# kulgurpower2-unrouted.net
KiCad netlist of a schematic drawn in EAGLE
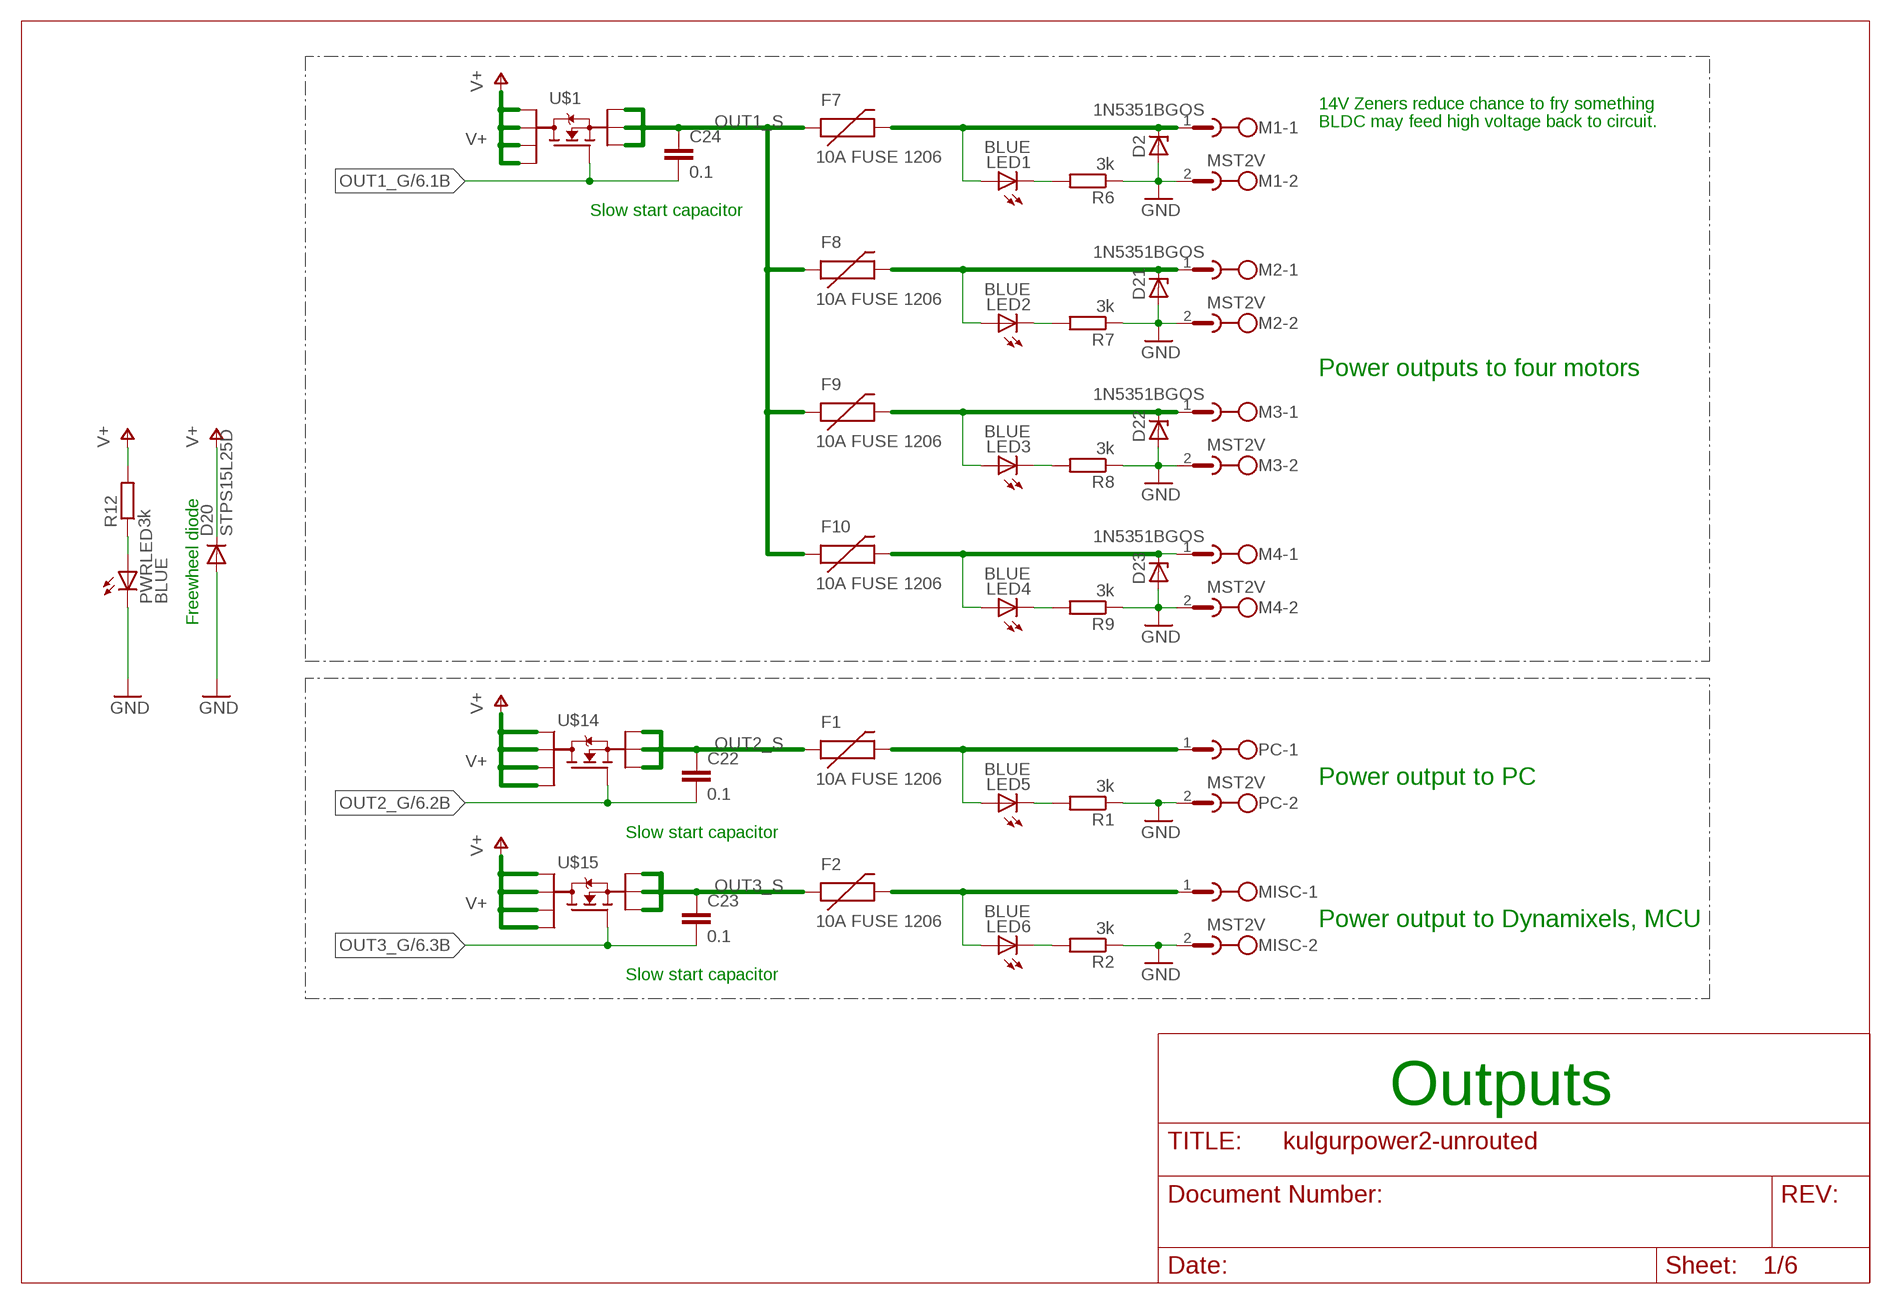
[diagram p0: schematic, sheet 1]
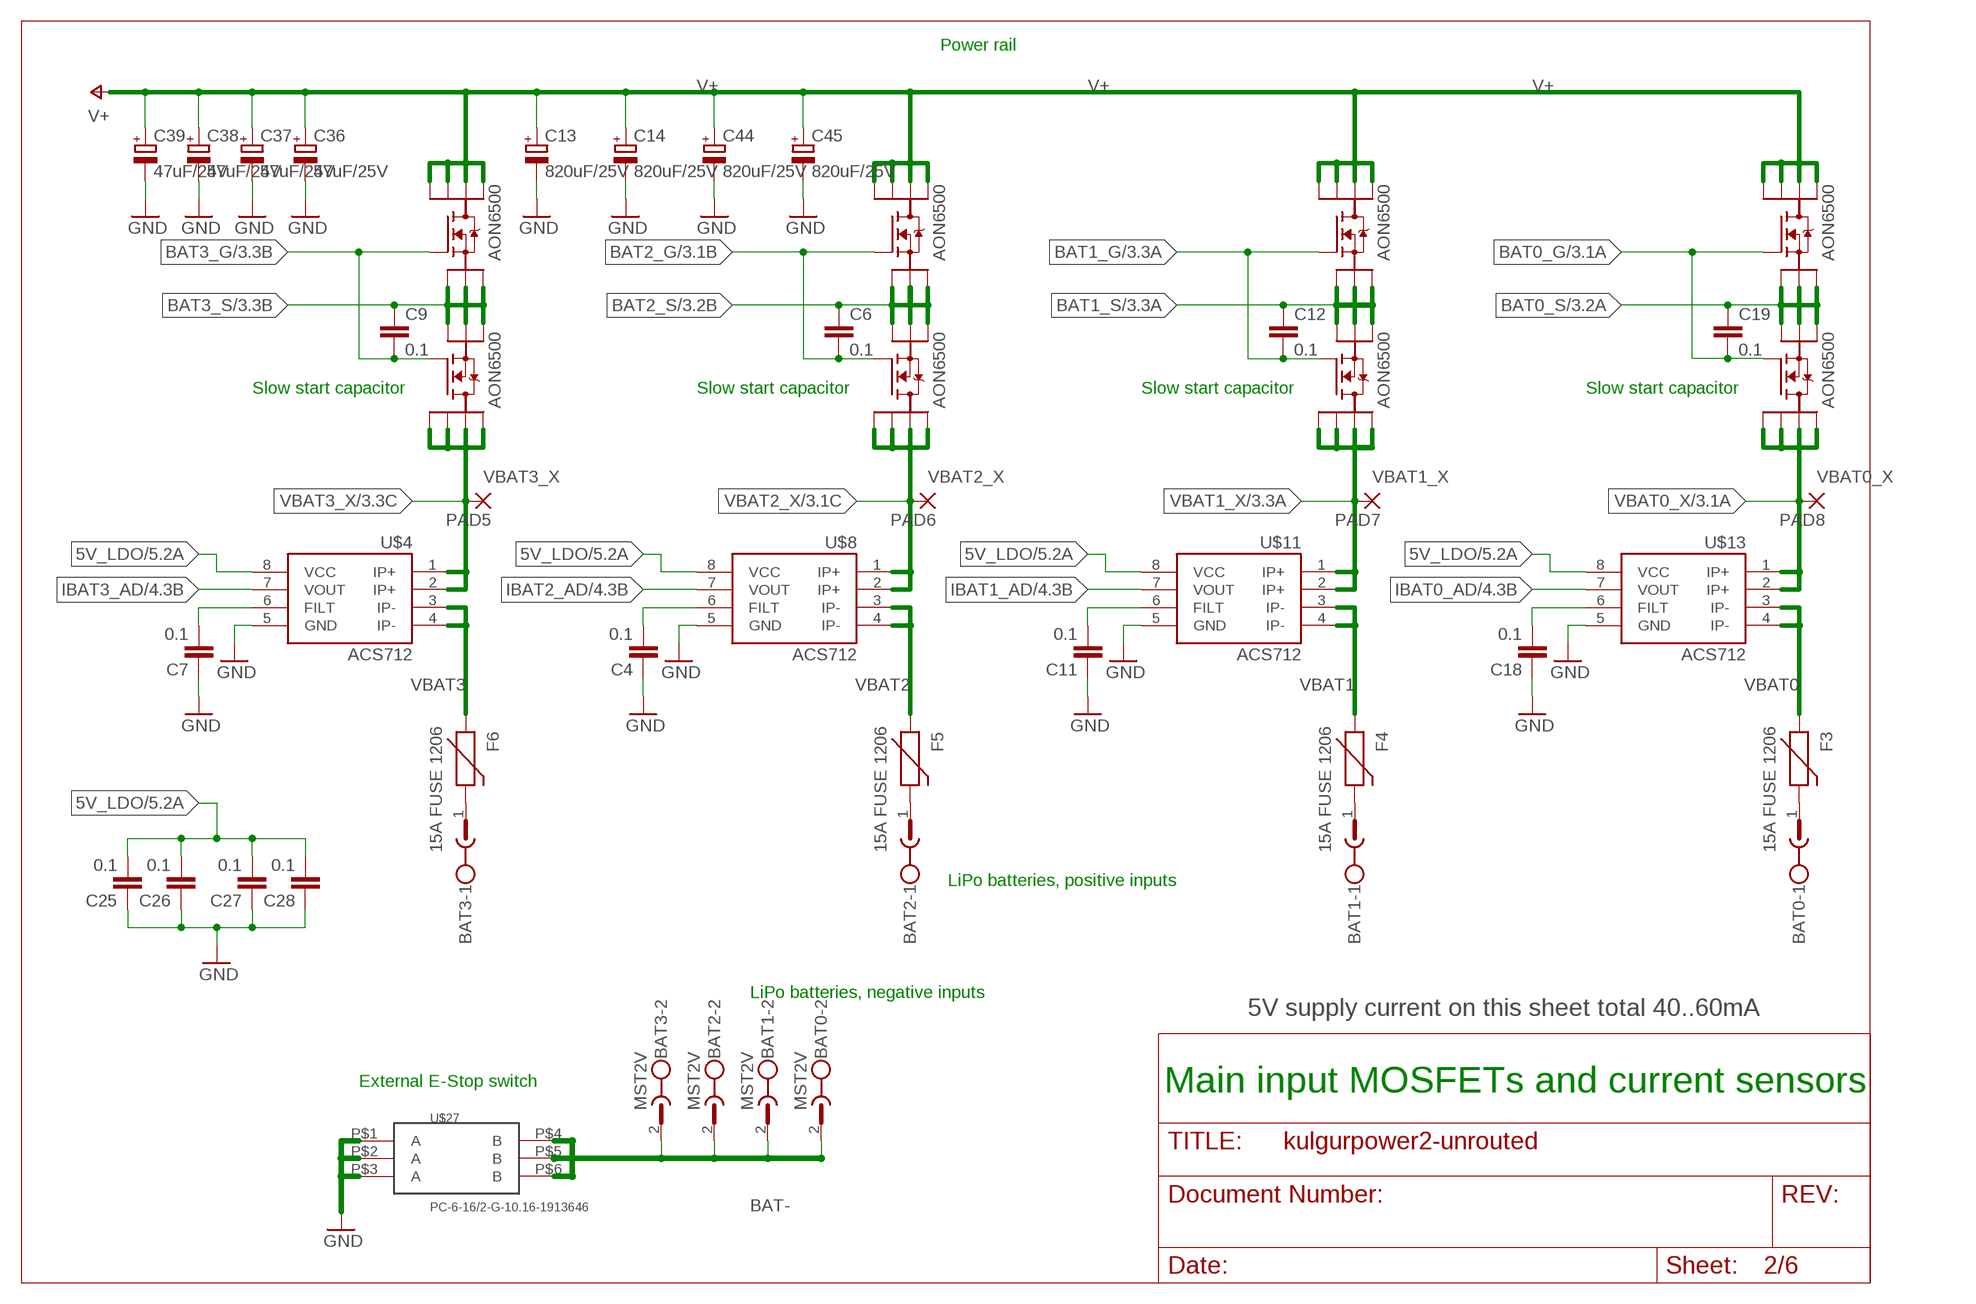
[diagram p1: schematic, sheet 2]
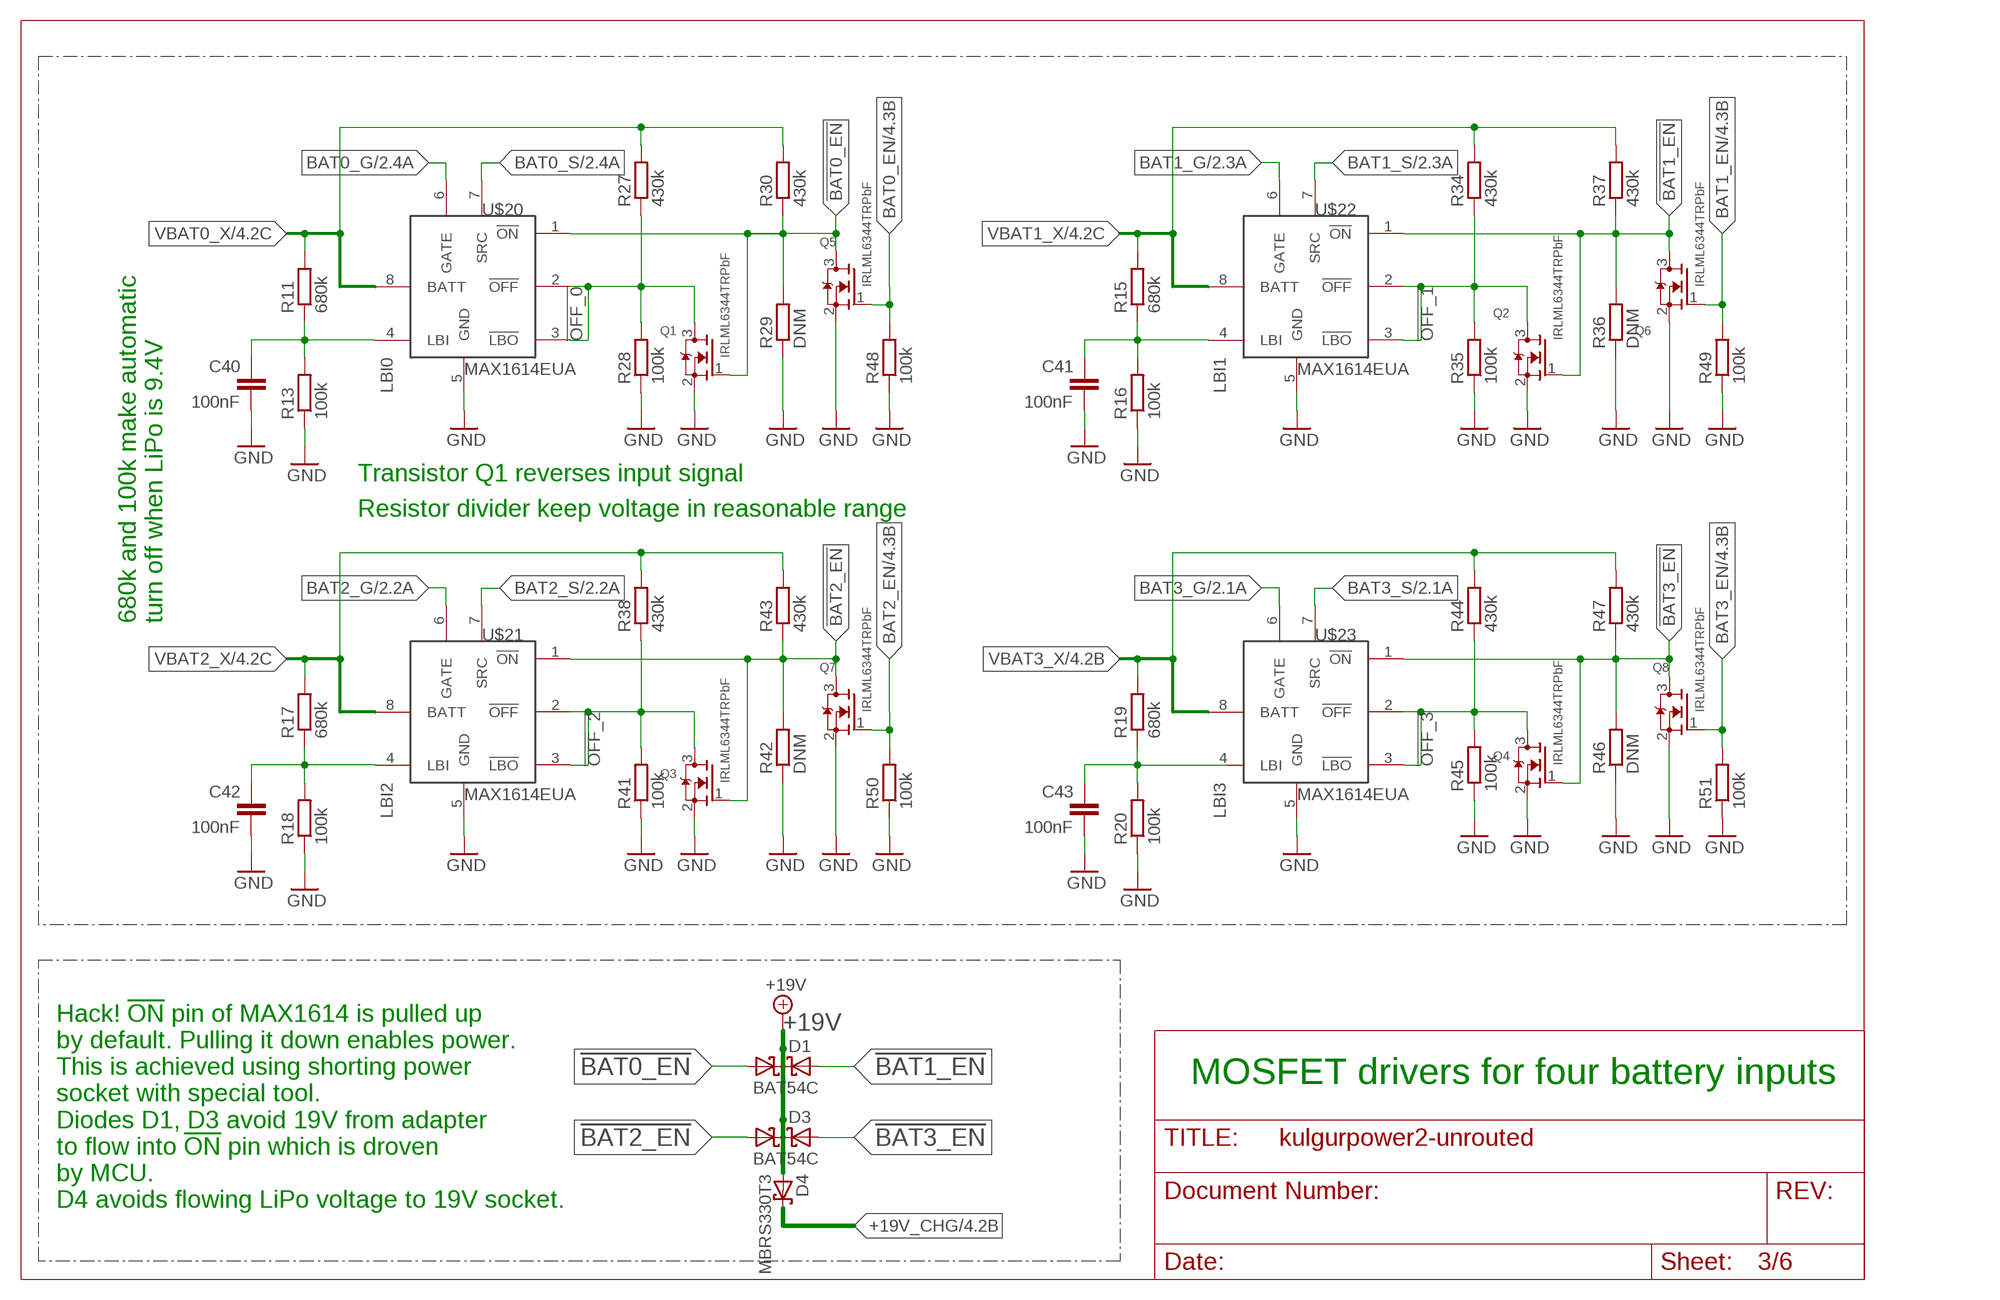
[diagram p2: schematic, sheet 3]
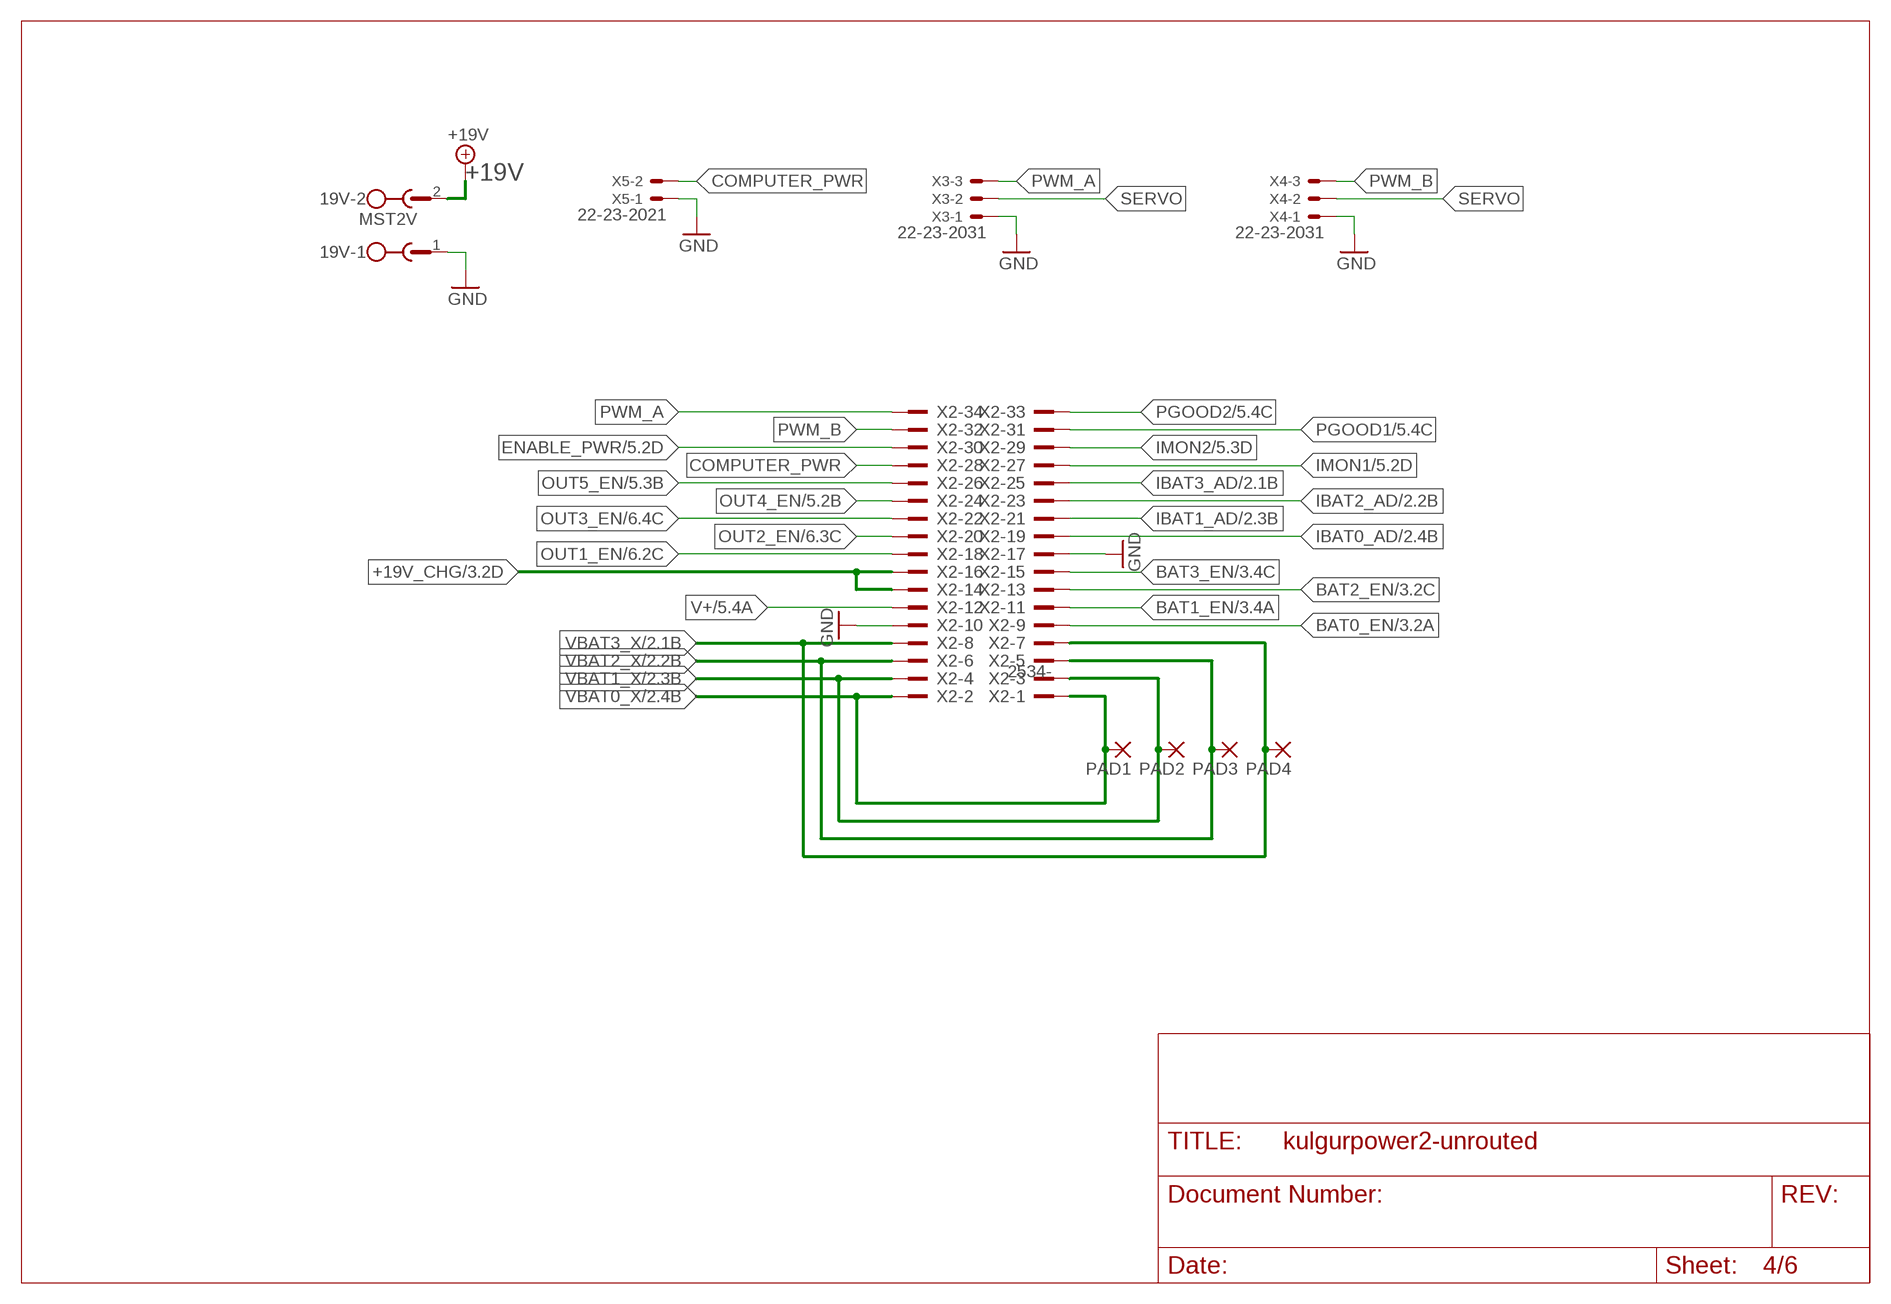
[diagram p3: schematic, sheet 4]
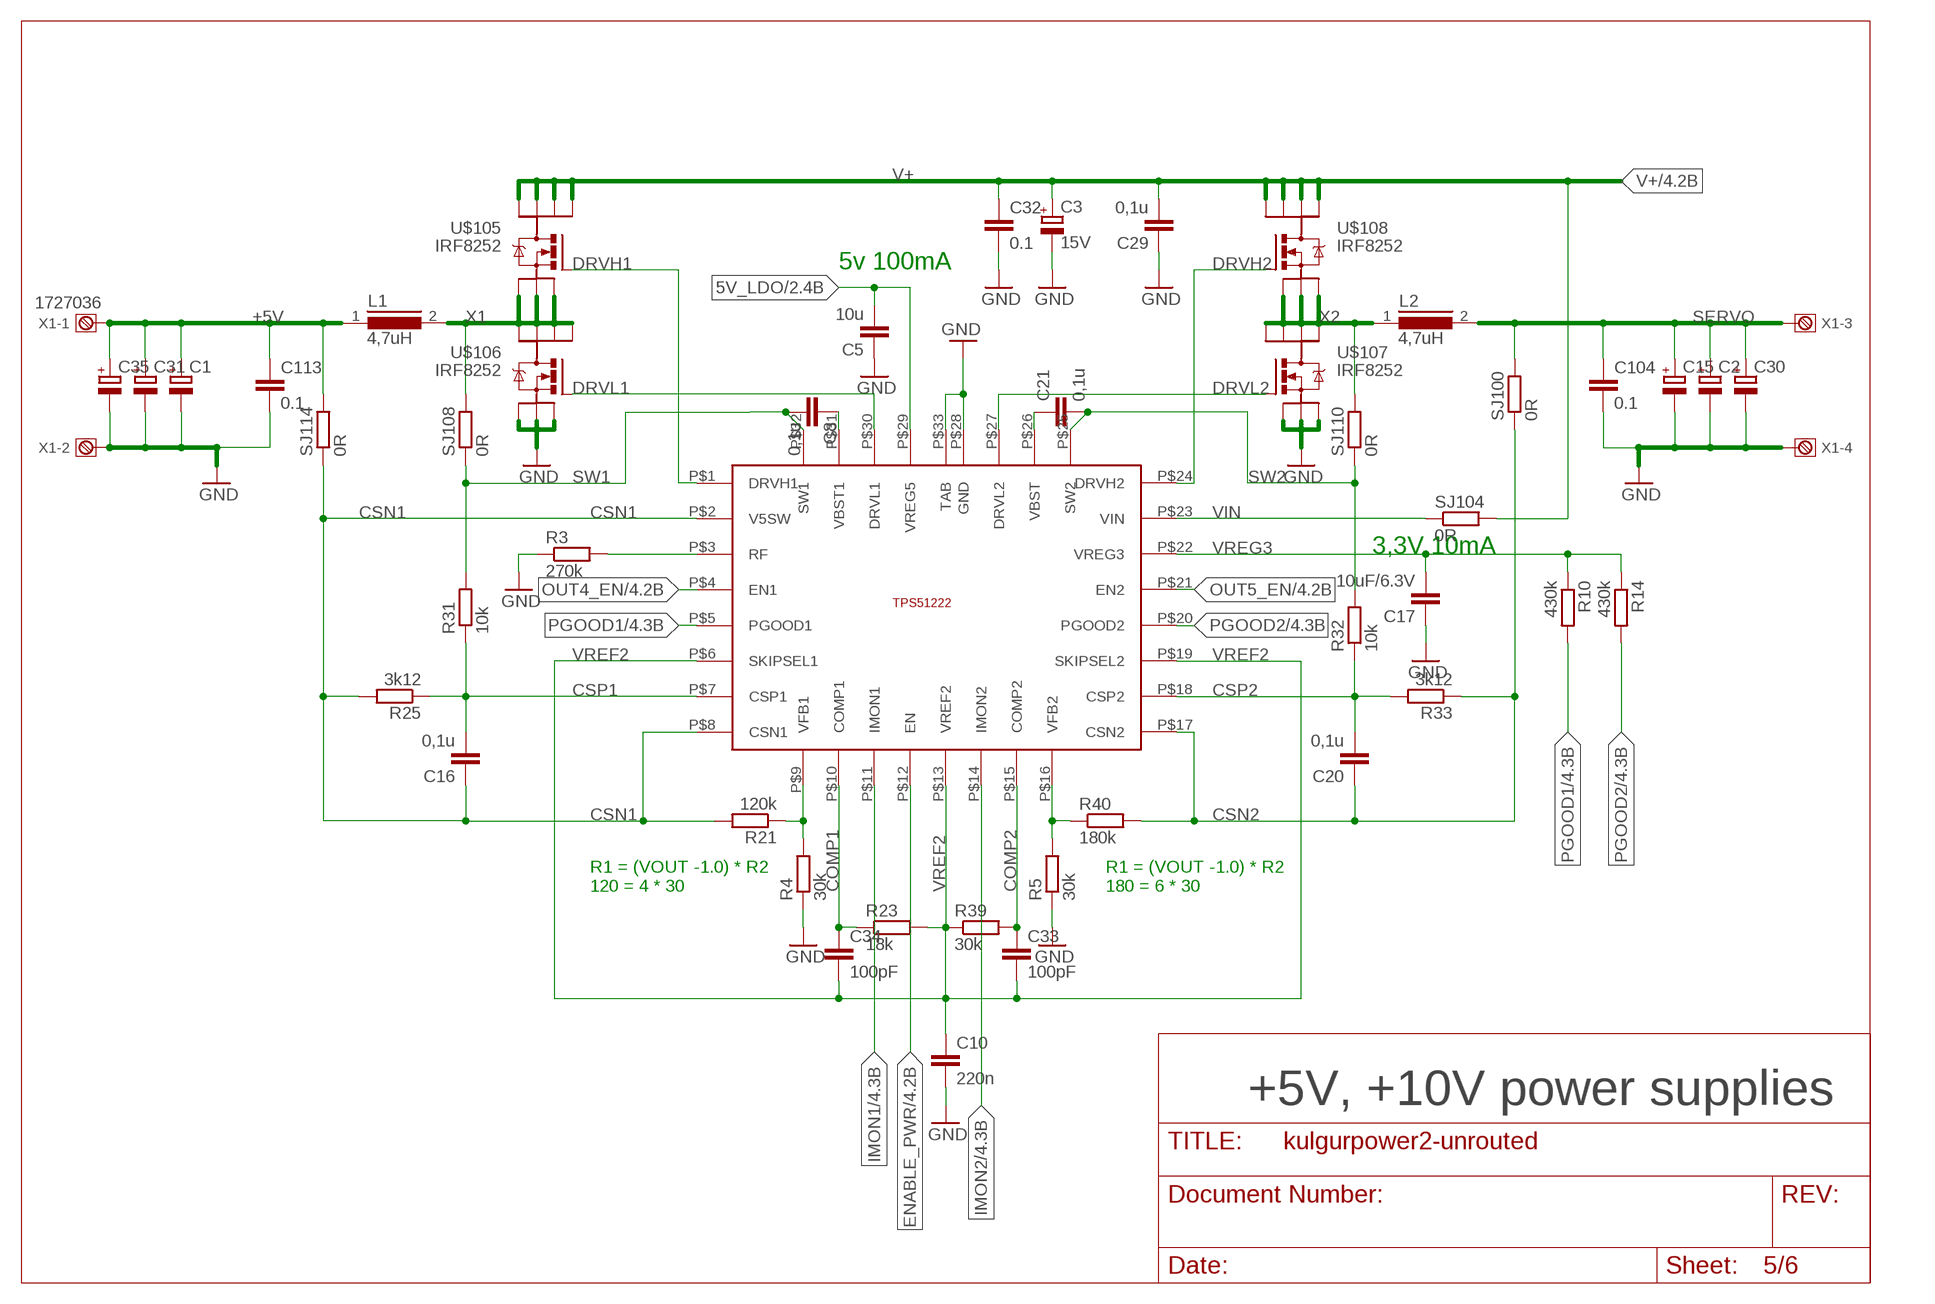
[diagram p4: schematic, sheet 5]
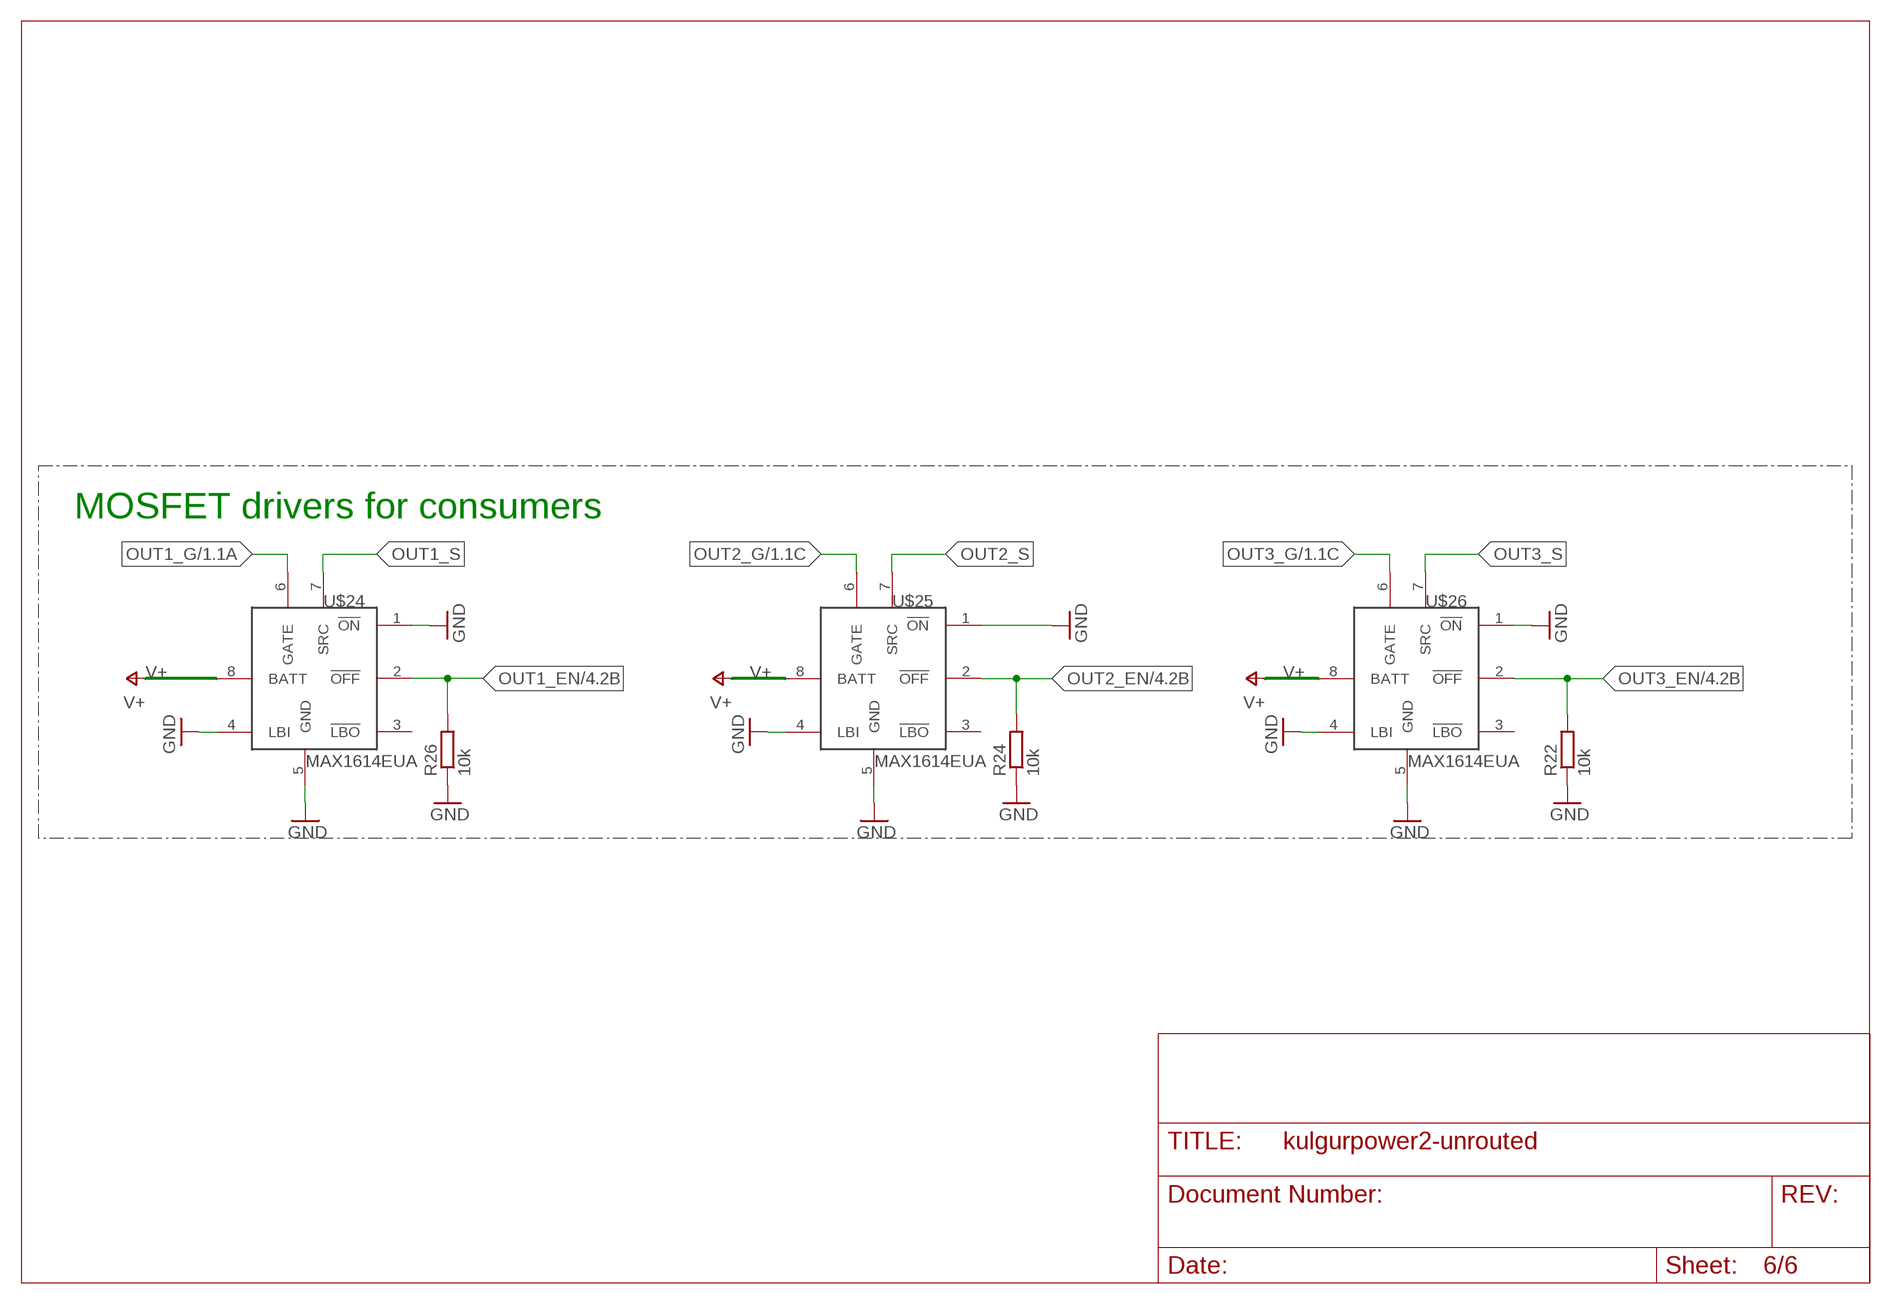
[diagram p5: schematic, sheet 6]

(export (version "E")
  (design (tool "Eeschema 10.0.6"))
  (components
    (comp (ref "C1")
      (value "CPOL-EUC/6032-28R")
      (footprint "eagle-import:C_6032-28R")
      (libsource (lib "eagle-import") (part "CPOL-EUC/6032-28R"))
    )
    (comp (ref "C2")
      (value "CPOL-EUC/6032-28R")
      (footprint "eagle-import:C_6032-28R")
      (libsource (lib "eagle-import") (part "CPOL-EUC/6032-28R"))
    )
    (comp (ref "C3")
      (value "15V")
      (footprint "eagle-import:C_6032-28R")
      (libsource (lib "eagle-import") (part "CPOL-EUC/6032-28R"))
    )
    (comp (ref "C5")
      (value "10u")
      (footprint "eagle-import:C1210")
      (libsource (lib "eagle-import") (part "C-EUC1210"))
    )
    (comp (ref "C8")
      (value "0,1u")
      (footprint "eagle-import:C0603")
      (libsource (lib "eagle-import") (part "C-EUC0603"))
    )
    (comp (ref "C10")
      (value "220n")
      (footprint "eagle-import:C0603")
      (libsource (lib "eagle-import") (part "C-EUC0603"))
    )
    (comp (ref "C15")
      (value "CPOL-EUC/6032-28R")
      (footprint "eagle-import:C_6032-28R")
      (libsource (lib "eagle-import") (part "CPOL-EUC/6032-28R"))
    )
    (comp (ref "C16")
      (value "0,1u")
      (footprint "eagle-import:C0603")
      (libsource (lib "eagle-import") (part "C-EUC0603"))
    )
    (comp (ref "C17")
      (value "10uF/6.3V")
      (footprint "eagle-import:C1210")
      (libsource (lib "eagle-import") (part "C-EUC1210"))
    )
    (comp (ref "C20")
      (value "0,1u")
      (footprint "eagle-import:C0603")
      (libsource (lib "eagle-import") (part "C-EUC0603"))
    )
    (comp (ref "C21")
      (value "0,1u")
      (footprint "eagle-import:C0603")
      (libsource (lib "eagle-import") (part "C-EUC0603"))
    )
    (comp (ref "C29")
      (value "0,1u")
      (footprint "eagle-import:C0603")
      (libsource (lib "eagle-import") (part "C-EUC0603"))
    )
    (comp (ref "C30")
      (value "CPOL-EUC/6032-28R")
      (footprint "eagle-import:C_6032-28R")
      (libsource (lib "eagle-import") (part "CPOL-EUC/6032-28R"))
    )
    (comp (ref "C31")
      (value "CPOL-EUC/6032-28R")
      (footprint "eagle-import:C_6032-28R")
      (libsource (lib "eagle-import") (part "CPOL-EUC/6032-28R"))
    )
    (comp (ref "C32")
      (value "0.1")
      (footprint "eagle-import:C0603")
      (libsource (lib "eagle-import") (part "C-EUC0603"))
    )
    (comp (ref "C33")
      (value "100pF")
      (footprint "eagle-import:0805")
      (libsource (lib "eagle-import") (part "CAP0805"))
    )
    (comp (ref "C34")
      (value "100pF")
      (footprint "eagle-import:0805")
      (libsource (lib "eagle-import") (part "CAP0805"))
    )
    (comp (ref "C35")
      (value "CPOL-EUC/6032-28R")
      (footprint "eagle-import:C_6032-28R")
      (libsource (lib "eagle-import") (part "CPOL-EUC/6032-28R"))
    )
    (comp (ref "C104")
      (value "0.1")
      (footprint "eagle-import:C0603")
      (libsource (lib "eagle-import") (part "C-EUC0603"))
    )
    (comp (ref "C113")
      (value "0.1")
      (footprint "eagle-import:C0603")
      (libsource (lib "eagle-import") (part "C-EUC0603"))
    )
    (comp (ref "L1")
      (value "4,7uH")
      (footprint "eagle-import:DR125")
      (libsource (lib "eagle-import") (part "DR125"))
    )
    (comp (ref "L2")
      (value "4,7uH")
      (footprint "eagle-import:DR125")
      (libsource (lib "eagle-import") (part "DR125"))
    )
    (comp (ref "R3")
      (value "270k")
      (footprint "eagle-import:R0603")
      (libsource (lib "eagle-import") (part "R-EU_R0603"))
    )
    (comp (ref "R4")
      (value "30k")
      (footprint "eagle-import:R0603")
      (libsource (lib "eagle-import") (part "R-EU_R0603"))
    )
    (comp (ref "R5")
      (value "30k")
      (footprint "eagle-import:R0603")
      (libsource (lib "eagle-import") (part "R-EU_R0603"))
    )
    (comp (ref "R10")
      (value "430k")
      (footprint "eagle-import:R0603")
      (libsource (lib "eagle-import") (part "R-EU_R0603"))
    )
    (comp (ref "R14")
      (value "430k")
      (footprint "eagle-import:R0603")
      (libsource (lib "eagle-import") (part "R-EU_R0603"))
    )
    (comp (ref "R21")
      (value "120k")
      (footprint "eagle-import:R0603")
      (libsource (lib "eagle-import") (part "R-EU_R0603"))
    )
    (comp (ref "R23")
      (value "18k")
      (footprint "eagle-import:R0603")
      (libsource (lib "eagle-import") (part "R-EU_R0603"))
    )
    (comp (ref "R25")
      (value "3k12")
      (footprint "eagle-import:R0603")
      (libsource (lib "eagle-import") (part "R-EU_R0603"))
    )
    (comp (ref "R31")
      (value "10k")
      (footprint "eagle-import:R0603")
      (libsource (lib "eagle-import") (part "R-EU_R0603"))
    )
    (comp (ref "R32")
      (value "10k")
      (footprint "eagle-import:R0603")
      (libsource (lib "eagle-import") (part "R-EU_R0603"))
    )
    (comp (ref "R33")
      (value "3k12")
      (footprint "eagle-import:R0603")
      (libsource (lib "eagle-import") (part "R-EU_R0603"))
    )
    (comp (ref "R39")
      (value "30k")
      (footprint "eagle-import:R0603")
      (libsource (lib "eagle-import") (part "R-EU_R0603"))
    )
    (comp (ref "R40")
      (value "180k")
      (footprint "eagle-import:R0603")
      (libsource (lib "eagle-import") (part "R-EU_R0603"))
    )
    (comp (ref "SJ100")
      (value "0R")
      (footprint "eagle-import:R0603")
      (libsource (lib "eagle-import") (part "R-EU_R0603"))
    )
    (comp (ref "SJ104")
      (value "0R")
      (footprint "eagle-import:R0603")
      (libsource (lib "eagle-import") (part "R-EU_R0603"))
    )
    (comp (ref "SJ108")
      (value "0R")
      (footprint "eagle-import:R0603")
      (libsource (lib "eagle-import") (part "R-EU_R0603"))
    )
    (comp (ref "SJ110")
      (value "0R")
      (footprint "eagle-import:R0603")
      (libsource (lib "eagle-import") (part "R-EU_R0603"))
    )
    (comp (ref "SJ114")
      (value "0R")
      (footprint "eagle-import:R0603")
      (libsource (lib "eagle-import") (part "R-EU_R0603"))
    )
    (comp (ref "U$17")
      (value "TPS51222RTVT")
      (footprint "eagle-import:QFN-32")
      (libsource (lib "eagle-import") (part "TPS51222RTVT"))
    )
    (comp (ref "U$105")
      (value "IRF8252")
      (footprint "eagle-import:SO8")
      (libsource (lib "eagle-import") (part "IRF8252"))
    )
    (comp (ref "U$106")
      (value "IRF8252")
      (footprint "eagle-import:SO8")
      (libsource (lib "eagle-import") (part "IRF8252"))
    )
    (comp (ref "U$107")
      (value "IRF8252")
      (footprint "eagle-import:SO8")
      (libsource (lib "eagle-import") (part "IRF8252"))
    )
    (comp (ref "U$108")
      (value "IRF8252")
      (footprint "eagle-import:SO8")
      (libsource (lib "eagle-import") (part "IRF8252"))
    )
    (comp (ref "X1")
      (value "1727036")
      (footprint "eagle-import:1727036")
      (fields (field (name "MF") "FARNELL"))
      (libsource (lib "eagle-import") (part "1727036"))
    )
    (comp (ref "19V")
      (value "MST2V")
      (footprint "eagle-import:MSTBV2")
      (libsource (lib "eagle-import") (part "MST2V"))
    )
    (comp (ref "PAD1")
      (value "1,6/0,9")
      (footprint "eagle-import:1,6_0,9")
      (libsource (lib "eagle-import") (part "1,6/0,9"))
    )
    (comp (ref "PAD2")
      (value "1,6/0,9")
      (footprint "eagle-import:1,6_0,9")
      (libsource (lib "eagle-import") (part "1,6/0,9"))
    )
    (comp (ref "PAD3")
      (value "1,6/0,9")
      (footprint "eagle-import:1,6_0,9")
      (libsource (lib "eagle-import") (part "1,6/0,9"))
    )
    (comp (ref "PAD4")
      (value "1,6/0,9")
      (footprint "eagle-import:1,6_0,9")
      (libsource (lib "eagle-import") (part "1,6/0,9"))
    )
    (comp (ref "X2")
      (value "2534-")
      (footprint "eagle-import:PAK100_2500-34")
      (libsource (lib "eagle-import") (part "2534-"))
    )
    (comp (ref "X3")
      (value "22-23-2031")
      (footprint "eagle-import:22-23-2031")
      (fields (field (name "MF") "MOLEX"))
      (libsource (lib "eagle-import") (part "22-23-2031"))
    )
    (comp (ref "X4")
      (value "22-23-2031")
      (footprint "eagle-import:22-23-2031")
      (fields (field (name "MF") "MOLEX"))
      (libsource (lib "eagle-import") (part "22-23-2031"))
    )
    (comp (ref "X5")
      (value "22-23-2021")
      (footprint "eagle-import:22-23-2021")
      (fields (field (name "MF") "MOLEX"))
      (libsource (lib "eagle-import") (part "22-23-2021"))
    )
    (comp (ref "C22")
      (value "0.1")
      (footprint "eagle-import:C0603")
      (libsource (lib "eagle-import") (part "C-EUC0603"))
    )
    (comp (ref "C23")
      (value "0.1")
      (footprint "eagle-import:C0603")
      (libsource (lib "eagle-import") (part "C-EUC0603"))
    )
    (comp (ref "C24")
      (value "0.1")
      (footprint "eagle-import:C0603")
      (libsource (lib "eagle-import") (part "C-EUC0603"))
    )
    (comp (ref "D2")
      (value "1N5351BGOS")
      (footprint "eagle-import:C1702-15")
      (libsource (lib "eagle-import") (part "1N5333"))
    )
    (comp (ref "D20")
      (value "STPS15L25D")
      (footprint "eagle-import:C221B1A")
      (libsource (lib "eagle-import") (part "DIODE-C221B1A"))
    )
    (comp (ref "D21")
      (value "1N5351BGOS")
      (footprint "eagle-import:C1702-15")
      (libsource (lib "eagle-import") (part "1N5333"))
    )
    (comp (ref "D22")
      (value "1N5351BGOS")
      (footprint "eagle-import:C1702-15")
      (libsource (lib "eagle-import") (part "1N5333"))
    )
    (comp (ref "D23")
      (value "1N5351BGOS")
      (footprint "eagle-import:C1702-15")
      (libsource (lib "eagle-import") (part "1N5333"))
    )
    (comp (ref "F1")
      (value "10A FUSE 1206")
      (footprint "eagle-import:PTC-1206")
      (libsource (lib "eagle-import") (part "PTCSMD"))
    )
    (comp (ref "F2")
      (value "10A FUSE 1206")
      (footprint "eagle-import:PTC-1206")
      (libsource (lib "eagle-import") (part "PTCSMD"))
    )
    (comp (ref "F7")
      (value "10A FUSE 1206")
      (footprint "eagle-import:PTC-1206")
      (libsource (lib "eagle-import") (part "PTCSMD"))
    )
    (comp (ref "F8")
      (value "10A FUSE 1206")
      (footprint "eagle-import:PTC-1206")
      (libsource (lib "eagle-import") (part "PTCSMD"))
    )
    (comp (ref "F9")
      (value "10A FUSE 1206")
      (footprint "eagle-import:PTC-1206")
      (libsource (lib "eagle-import") (part "PTCSMD"))
    )
    (comp (ref "F10")
      (value "10A FUSE 1206")
      (footprint "eagle-import:PTC-1206")
      (libsource (lib "eagle-import") (part "PTCSMD"))
    )
    (comp (ref "LED1")
      (value "BLUE")
      (footprint "eagle-import:CHIP-LED0603")
      (libsource (lib "eagle-import") (part "LEDCHIP-LED0603"))
    )
    (comp (ref "LED2")
      (value "BLUE")
      (footprint "eagle-import:CHIP-LED0603")
      (libsource (lib "eagle-import") (part "LEDCHIP-LED0603"))
    )
    (comp (ref "LED3")
      (value "BLUE")
      (footprint "eagle-import:CHIP-LED0603")
      (libsource (lib "eagle-import") (part "LEDCHIP-LED0603"))
    )
    (comp (ref "LED4")
      (value "BLUE")
      (footprint "eagle-import:CHIP-LED0603")
      (libsource (lib "eagle-import") (part "LEDCHIP-LED0603"))
    )
    (comp (ref "LED5")
      (value "BLUE")
      (footprint "eagle-import:CHIP-LED0603")
      (libsource (lib "eagle-import") (part "LEDCHIP-LED0603"))
    )
    (comp (ref "LED6")
      (value "BLUE")
      (footprint "eagle-import:CHIP-LED0603")
      (libsource (lib "eagle-import") (part "LEDCHIP-LED0603"))
    )
    (comp (ref "M1")
      (value "MST2V")
      (footprint "eagle-import:MSTBV2")
      (libsource (lib "eagle-import") (part "MST2V"))
    )
    (comp (ref "M2")
      (value "MST2V")
      (footprint "eagle-import:MSTBV2")
      (libsource (lib "eagle-import") (part "MST2V"))
    )
    (comp (ref "M3")
      (value "MST2V")
      (footprint "eagle-import:MSTBV2")
      (libsource (lib "eagle-import") (part "MST2V"))
    )
    (comp (ref "M4")
      (value "MST2V")
      (footprint "eagle-import:MSTBV2")
      (libsource (lib "eagle-import") (part "MST2V"))
    )
    (comp (ref "MISC")
      (value "MST2V")
      (footprint "eagle-import:MSTBV2")
      (libsource (lib "eagle-import") (part "MST2V"))
    )
    (comp (ref "PC")
      (value "MST2V")
      (footprint "eagle-import:MSTBV2")
      (libsource (lib "eagle-import") (part "MST2V"))
    )
    (comp (ref "PWRLED")
      (value "BLUE")
      (footprint "eagle-import:CHIP-LED0603")
      (libsource (lib "eagle-import") (part "LEDCHIP-LED0603"))
    )
    (comp (ref "R1")
      (value "3k")
      (footprint "eagle-import:R0603")
      (libsource (lib "eagle-import") (part "R-EU_R0603"))
    )
    (comp (ref "R2")
      (value "3k")
      (footprint "eagle-import:R0603")
      (libsource (lib "eagle-import") (part "R-EU_R0603"))
    )
    (comp (ref "R6")
      (value "3k")
      (footprint "eagle-import:R0603")
      (libsource (lib "eagle-import") (part "R-EU_R0603"))
    )
    (comp (ref "R7")
      (value "3k")
      (footprint "eagle-import:R0603")
      (libsource (lib "eagle-import") (part "R-EU_R0603"))
    )
    (comp (ref "R8")
      (value "3k")
      (footprint "eagle-import:R0603")
      (libsource (lib "eagle-import") (part "R-EU_R0603"))
    )
    (comp (ref "R9")
      (value "3k")
      (footprint "eagle-import:R0603")
      (libsource (lib "eagle-import") (part "R-EU_R0603"))
    )
    (comp (ref "R12")
      (value "3k")
      (footprint "eagle-import:R0603")
      (libsource (lib "eagle-import") (part "R-EU_R0603"))
    )
    (comp (ref "U$1")
      (value "AON6500")
      (footprint "eagle-import:POWER56")
      (libsource (lib "eagle-import") (part "FDMS8558S"))
    )
    (comp (ref "U$14")
      (value "AON6500")
      (footprint "eagle-import:POWER56")
      (libsource (lib "eagle-import") (part "FDMS8558S"))
    )
    (comp (ref "U$15")
      (value "AON6500")
      (footprint "eagle-import:POWER56")
      (libsource (lib "eagle-import") (part "FDMS8558S"))
    )
    (comp (ref "R22")
      (value "10k")
      (footprint "eagle-import:R0603")
      (libsource (lib "eagle-import") (part "R-EU_R0603"))
    )
    (comp (ref "R24")
      (value "10k")
      (footprint "eagle-import:R0603")
      (libsource (lib "eagle-import") (part "R-EU_R0603"))
    )
    (comp (ref "R26")
      (value "10k")
      (footprint "eagle-import:R0603")
      (libsource (lib "eagle-import") (part "R-EU_R0603"))
    )
    (comp (ref "U$24")
      (value "MAX1614EUA")
      (footprint "eagle-import:MAX1614EUA")
      (libsource (lib "eagle-import") (part "MAX1614EUA"))
    )
    (comp (ref "U$25")
      (value "MAX1614EUA")
      (footprint "eagle-import:MAX1614EUA")
      (libsource (lib "eagle-import") (part "MAX1614EUA"))
    )
    (comp (ref "U$26")
      (value "MAX1614EUA")
      (footprint "eagle-import:MAX1614EUA")
      (libsource (lib "eagle-import") (part "MAX1614EUA"))
    )
    (comp (ref "C40")
      (value "100nF")
      (footprint "eagle-import:C0603")
      (libsource (lib "eagle-import") (part "C-EUC0603"))
    )
    (comp (ref "C41")
      (value "100nF")
      (footprint "eagle-import:C0603")
      (libsource (lib "eagle-import") (part "C-EUC0603"))
    )
    (comp (ref "C42")
      (value "100nF")
      (footprint "eagle-import:C0603")
      (libsource (lib "eagle-import") (part "C-EUC0603"))
    )
    (comp (ref "C43")
      (value "100nF")
      (footprint "eagle-import:C0603")
      (libsource (lib "eagle-import") (part "C-EUC0603"))
    )
    (comp (ref "D1")
      (value "BAT54C")
      (footprint "eagle-import:SOT23")
      (libsource (lib "eagle-import") (part "BAT54C"))
    )
    (comp (ref "D3")
      (value "BAT54C")
      (footprint "eagle-import:SOT23")
      (libsource (lib "eagle-import") (part "BAT54C"))
    )
    (comp (ref "D4")
      (value "MBRS330T3")
      (footprint "eagle-import:SMC")
      (libsource (lib "eagle-import") (part "MBRS30T33"))
    )
    (comp (ref "Q1")
      (value "IRLML6344TRPbF")
      (footprint "eagle-import:SOT23")
      (libsource (lib "eagle-import") (part "MOSFET-NREFLOW"))
    )
    (comp (ref "Q2")
      (value "IRLML6344TRPbF")
      (footprint "eagle-import:SOT23")
      (libsource (lib "eagle-import") (part "MOSFET-NREFLOW"))
    )
    (comp (ref "Q3")
      (value "IRLML6344TRPbF")
      (footprint "eagle-import:SOT23")
      (libsource (lib "eagle-import") (part "MOSFET-NREFLOW"))
    )
    (comp (ref "Q4")
      (value "IRLML6344TRPbF")
      (footprint "eagle-import:SOT23")
      (libsource (lib "eagle-import") (part "MOSFET-NREFLOW"))
    )
    (comp (ref "Q5")
      (value "IRLML6344TRPbF")
      (footprint "eagle-import:SOT23")
      (libsource (lib "eagle-import") (part "MOSFET-NREFLOW"))
    )
    (comp (ref "Q6")
      (value "IRLML6344TRPbF")
      (footprint "eagle-import:SOT23")
      (libsource (lib "eagle-import") (part "MOSFET-NREFLOW"))
    )
    (comp (ref "Q7")
      (value "IRLML6344TRPbF")
      (footprint "eagle-import:SOT23")
      (libsource (lib "eagle-import") (part "MOSFET-NREFLOW"))
    )
    (comp (ref "Q8")
      (value "IRLML6344TRPbF")
      (footprint "eagle-import:SOT23")
      (libsource (lib "eagle-import") (part "MOSFET-NREFLOW"))
    )
    (comp (ref "R11")
      (value "680k")
      (footprint "eagle-import:R0603")
      (libsource (lib "eagle-import") (part "R-EU_R0603"))
    )
    (comp (ref "R13")
      (value "100k")
      (footprint "eagle-import:R0603")
      (libsource (lib "eagle-import") (part "R-EU_R0603"))
    )
    (comp (ref "R15")
      (value "680k")
      (footprint "eagle-import:R0603")
      (libsource (lib "eagle-import") (part "R-EU_R0603"))
    )
    (comp (ref "R16")
      (value "100k")
      (footprint "eagle-import:R0603")
      (libsource (lib "eagle-import") (part "R-EU_R0603"))
    )
    (comp (ref "R17")
      (value "680k")
      (footprint "eagle-import:R0603")
      (libsource (lib "eagle-import") (part "R-EU_R0603"))
    )
    (comp (ref "R18")
      (value "100k")
      (footprint "eagle-import:R0603")
      (libsource (lib "eagle-import") (part "R-EU_R0603"))
    )
    (comp (ref "R19")
      (value "680k")
      (footprint "eagle-import:R0603")
      (libsource (lib "eagle-import") (part "R-EU_R0603"))
    )
    (comp (ref "R20")
      (value "100k")
      (footprint "eagle-import:R0603")
      (libsource (lib "eagle-import") (part "R-EU_R0603"))
    )
    (comp (ref "R27")
      (value "430k")
      (footprint "eagle-import:R0603")
      (libsource (lib "eagle-import") (part "R-EU_R0603"))
    )
    (comp (ref "R28")
      (value "100k")
      (footprint "eagle-import:R0603")
      (libsource (lib "eagle-import") (part "R-EU_R0603"))
    )
    (comp (ref "R29")
      (value "DNM")
      (footprint "eagle-import:R0603")
      (libsource (lib "eagle-import") (part "R-EU_R0603"))
    )
    (comp (ref "R30")
      (value "430k")
      (footprint "eagle-import:R0603")
      (libsource (lib "eagle-import") (part "R-EU_R0603"))
    )
    (comp (ref "R34")
      (value "430k")
      (footprint "eagle-import:R0603")
      (libsource (lib "eagle-import") (part "R-EU_R0603"))
    )
    (comp (ref "R35")
      (value "100k")
      (footprint "eagle-import:R0603")
      (libsource (lib "eagle-import") (part "R-EU_R0603"))
    )
    (comp (ref "R36")
      (value "DNM")
      (footprint "eagle-import:R0603")
      (libsource (lib "eagle-import") (part "R-EU_R0603"))
    )
    (comp (ref "R37")
      (value "430k")
      (footprint "eagle-import:R0603")
      (libsource (lib "eagle-import") (part "R-EU_R0603"))
    )
    (comp (ref "R38")
      (value "430k")
      (footprint "eagle-import:R0603")
      (libsource (lib "eagle-import") (part "R-EU_R0603"))
    )
    (comp (ref "R41")
      (value "100k")
      (footprint "eagle-import:R0603")
      (libsource (lib "eagle-import") (part "R-EU_R0603"))
    )
    (comp (ref "R42")
      (value "DNM")
      (footprint "eagle-import:R0603")
      (libsource (lib "eagle-import") (part "R-EU_R0603"))
    )
    (comp (ref "R43")
      (value "430k")
      (footprint "eagle-import:R0603")
      (libsource (lib "eagle-import") (part "R-EU_R0603"))
    )
    (comp (ref "R44")
      (value "430k")
      (footprint "eagle-import:R0603")
      (libsource (lib "eagle-import") (part "R-EU_R0603"))
    )
    (comp (ref "R45")
      (value "100k")
      (footprint "eagle-import:R0603")
      (libsource (lib "eagle-import") (part "R-EU_R0603"))
    )
    (comp (ref "R46")
      (value "DNM")
      (footprint "eagle-import:R0603")
      (libsource (lib "eagle-import") (part "R-EU_R0603"))
    )
    (comp (ref "R47")
      (value "430k")
      (footprint "eagle-import:R0603")
      (libsource (lib "eagle-import") (part "R-EU_R0603"))
    )
    (comp (ref "R48")
      (value "100k")
      (footprint "eagle-import:R0603")
      (libsource (lib "eagle-import") (part "R-EU_R0603"))
    )
    (comp (ref "R49")
      (value "100k")
      (footprint "eagle-import:R0603")
      (libsource (lib "eagle-import") (part "R-EU_R0603"))
    )
    (comp (ref "R50")
      (value "100k")
      (footprint "eagle-import:R0603")
      (libsource (lib "eagle-import") (part "R-EU_R0603"))
    )
    (comp (ref "R51")
      (value "100k")
      (footprint "eagle-import:R0603")
      (libsource (lib "eagle-import") (part "R-EU_R0603"))
    )
    (comp (ref "U$20")
      (value "MAX1614EUA")
      (footprint "eagle-import:MAX1614EUA")
      (libsource (lib "eagle-import") (part "MAX1614EUA"))
    )
    (comp (ref "U$21")
      (value "MAX1614EUA")
      (footprint "eagle-import:MAX1614EUA")
      (libsource (lib "eagle-import") (part "MAX1614EUA"))
    )
    (comp (ref "U$22")
      (value "MAX1614EUA")
      (footprint "eagle-import:MAX1614EUA")
      (libsource (lib "eagle-import") (part "MAX1614EUA"))
    )
    (comp (ref "U$23")
      (value "MAX1614EUA")
      (footprint "eagle-import:MAX1614EUA")
      (libsource (lib "eagle-import") (part "MAX1614EUA"))
    )
    (comp (ref "BAT0")
      (value "MST2V")
      (footprint "eagle-import:MSTBV2")
      (libsource (lib "eagle-import") (part "MST2V"))
    )
    (comp (ref "BAT1")
      (value "MST2V")
      (footprint "eagle-import:MSTBV2")
      (libsource (lib "eagle-import") (part "MST2V"))
    )
    (comp (ref "BAT2")
      (value "MST2V")
      (footprint "eagle-import:MSTBV2")
      (libsource (lib "eagle-import") (part "MST2V"))
    )
    (comp (ref "BAT3")
      (value "MST2V")
      (footprint "eagle-import:MSTBV2")
      (libsource (lib "eagle-import") (part "MST2V"))
    )
    (comp (ref "C4")
      (value "0.1")
      (footprint "eagle-import:C0603")
      (libsource (lib "eagle-import") (part "C-EUC0603"))
    )
    (comp (ref "C6")
      (value "0.1")
      (footprint "eagle-import:C0603")
      (libsource (lib "eagle-import") (part "C-EUC0603"))
    )
    (comp (ref "C7")
      (value "0.1")
      (footprint "eagle-import:C0603")
      (libsource (lib "eagle-import") (part "C-EUC0603"))
    )
    (comp (ref "C9")
      (value "0.1")
      (footprint "eagle-import:C0603")
      (libsource (lib "eagle-import") (part "C-EUC0603"))
    )
    (comp (ref "C11")
      (value "0.1")
      (footprint "eagle-import:C0603")
      (libsource (lib "eagle-import") (part "C-EUC0603"))
    )
    (comp (ref "C12")
      (value "0.1")
      (footprint "eagle-import:C0603")
      (libsource (lib "eagle-import") (part "C-EUC0603"))
    )
    (comp (ref "C13")
      (value "820uF/25V")
      (footprint "eagle-import:153CLV-1014")
      (libsource (lib "eagle-import") (part "CPOL-EU153CLV-1014"))
    )
    (comp (ref "C14")
      (value "820uF/25V")
      (footprint "eagle-import:153CLV-1014")
      (libsource (lib "eagle-import") (part "CPOL-EU153CLV-1014"))
    )
    (comp (ref "C18")
      (value "0.1")
      (footprint "eagle-import:C0603")
      (libsource (lib "eagle-import") (part "C-EUC0603"))
    )
    (comp (ref "C19")
      (value "0.1")
      (footprint "eagle-import:C0603")
      (libsource (lib "eagle-import") (part "C-EUC0603"))
    )
    (comp (ref "C25")
      (value "0.1")
      (footprint "eagle-import:C0603")
      (libsource (lib "eagle-import") (part "C-EUC0603"))
    )
    (comp (ref "C26")
      (value "0.1")
      (footprint "eagle-import:C0603")
      (libsource (lib "eagle-import") (part "C-EUC0603"))
    )
    (comp (ref "C27")
      (value "0.1")
      (footprint "eagle-import:C0603")
      (libsource (lib "eagle-import") (part "C-EUC0603"))
    )
    (comp (ref "C28")
      (value "0.1")
      (footprint "eagle-import:C0603")
      (libsource (lib "eagle-import") (part "C-EUC0603"))
    )
    (comp (ref "C36")
      (value "47uF/25V")
      (footprint "eagle-import:C_6032-28R")
      (libsource (lib "eagle-import") (part "CPOL-EUC/6032-28R"))
    )
    (comp (ref "C37")
      (value "47uF/25V")
      (footprint "eagle-import:C_6032-28R")
      (libsource (lib "eagle-import") (part "CPOL-EUC/6032-28R"))
    )
    (comp (ref "C38")
      (value "47uF/25V")
      (footprint "eagle-import:175TMP-0810")
      (libsource (lib "eagle-import") (part "CPOL-EU175TMP-0810"))
    )
    (comp (ref "C39")
      (value "47uF/25V")
      (footprint "eagle-import:175TMP-0810")
      (libsource (lib "eagle-import") (part "CPOL-EU175TMP-0810"))
    )
    (comp (ref "C44")
      (value "820uF/25V")
      (footprint "eagle-import:153CLV-1014")
      (libsource (lib "eagle-import") (part "CPOL-EU153CLV-1014"))
    )
    (comp (ref "C45")
      (value "820uF/25V")
      (footprint "eagle-import:153CLV-1014")
      (libsource (lib "eagle-import") (part "CPOL-EU153CLV-1014"))
    )
    (comp (ref "F3")
      (value "15A FUSE 1206")
      (footprint "eagle-import:PTC-1206")
      (libsource (lib "eagle-import") (part "PTCSMD"))
    )
    (comp (ref "F4")
      (value "15A FUSE 1206")
      (footprint "eagle-import:PTC-1206")
      (libsource (lib "eagle-import") (part "PTCSMD"))
    )
    (comp (ref "F5")
      (value "15A FUSE 1206")
      (footprint "eagle-import:PTC-1206")
      (libsource (lib "eagle-import") (part "PTCSMD"))
    )
    (comp (ref "F6")
      (value "15A FUSE 1206")
      (footprint "eagle-import:PTC-1206")
      (libsource (lib "eagle-import") (part "PTCSMD"))
    )
    (comp (ref "PAD5")
      (value "1,6/0,9")
      (footprint "eagle-import:1,6_0,9")
      (libsource (lib "eagle-import") (part "1,6/0,9"))
    )
    (comp (ref "PAD6")
      (value "1,6/0,9")
      (footprint "eagle-import:1,6_0,9")
      (libsource (lib "eagle-import") (part "1,6/0,9"))
    )
    (comp (ref "PAD7")
      (value "1,6/0,9")
      (footprint "eagle-import:1,6_0,9")
      (libsource (lib "eagle-import") (part "1,6/0,9"))
    )
    (comp (ref "PAD8")
      (value "1,6/0,9")
      (footprint "eagle-import:1,6_0,9")
      (libsource (lib "eagle-import") (part "1,6/0,9"))
    )
    (comp (ref "U$2")
      (value "AON6500")
      (footprint "eagle-import:POWER56")
      (libsource (lib "eagle-import") (part "FDMS8558S"))
    )
    (comp (ref "U$3")
      (value "AON6500")
      (footprint "eagle-import:POWER56")
      (libsource (lib "eagle-import") (part "FDMS8558S"))
    )
    (comp (ref "U$4")
      (value "ACS712")
      (footprint "eagle-import:SO08")
      (libsource (lib "eagle-import") (part "ACS712"))
    )
    (comp (ref "U$5")
      (value "AON6500")
      (footprint "eagle-import:POWER56")
      (libsource (lib "eagle-import") (part "FDMS8558S"))
    )
    (comp (ref "U$6")
      (value "AON6500")
      (footprint "eagle-import:POWER56")
      (libsource (lib "eagle-import") (part "FDMS8558S"))
    )
    (comp (ref "U$7")
      (value "AON6500")
      (footprint "eagle-import:POWER56")
      (libsource (lib "eagle-import") (part "FDMS8558S"))
    )
    (comp (ref "U$8")
      (value "ACS712")
      (footprint "eagle-import:SO08")
      (libsource (lib "eagle-import") (part "ACS712"))
    )
    (comp (ref "U$9")
      (value "AON6500")
      (footprint "eagle-import:POWER56")
      (libsource (lib "eagle-import") (part "FDMS8558S"))
    )
    (comp (ref "U$10")
      (value "AON6500")
      (footprint "eagle-import:POWER56")
      (libsource (lib "eagle-import") (part "FDMS8558S"))
    )
    (comp (ref "U$11")
      (value "ACS712")
      (footprint "eagle-import:SO08")
      (libsource (lib "eagle-import") (part "ACS712"))
    )
    (comp (ref "U$12")
      (value "AON6500")
      (footprint "eagle-import:POWER56")
      (libsource (lib "eagle-import") (part "FDMS8558S"))
    )
    (comp (ref "U$13")
      (value "ACS712")
      (footprint "eagle-import:SO08")
      (libsource (lib "eagle-import") (part "ACS712"))
    )
    (comp (ref "U$27")
      (value "PC-6-16/2-G-10.16-1913646")
      (footprint "eagle-import:PC-6-16_2-G-10.16")
      (libsource (lib "eagle-import") (part "PC-6-16/2-G-10.16-1913646"))
    )
  )
  (nets
    (net (code "1") (name "+5V") (class "Default")
      (node (ref "C1") (pin "+") (pinfunction "+_+") (pintype "passive"))
      (node (ref "C113") (pin "1") (pinfunction "1_1") (pintype "passive"))
      (node (ref "C31") (pin "+") (pinfunction "+_+") (pintype "passive"))
      (node (ref "C35") (pin "+") (pinfunction "+_+") (pintype "passive"))
      (node (ref "L1") (pin "1") (pinfunction "1_1") (pintype "passive"))
      (node (ref "SJ114") (pin "2") (pinfunction "2_2") (pintype "passive"))
      (node (ref "X1") (pin "1") (pinfunction "1_1") (pintype "passive"))
    )
    (net (code "2") (name "+19V") (class "Default")
      (node (ref "19V") (pin "2") (pinfunction "1_2") (pintype "passive"))
      (node (ref "D1") (pin "3") (pinfunction "CC_3") (pintype "passive"))
      (node (ref "D3") (pin "3") (pinfunction "CC_3") (pintype "passive"))
      (node (ref "D4") (pin "A") (pinfunction "A_A") (pintype "passive"))
    )
    (net (code "3") (name "+19V_CHG") (class "Default")
      (node (ref "D4") (pin "C") (pinfunction "C_C") (pintype "passive"))
      (node (ref "X2") (pin "14") (pinfunction "KL_14") (pintype "passive"))
      (node (ref "X2") (pin "16") (pinfunction "KL_16") (pintype "passive"))
    )
    (net (code "4") (name "5V_LDO") (class "Default")
      (node (ref "C25") (pin "2") (pinfunction "2_2") (pintype "passive"))
      (node (ref "C26") (pin "2") (pinfunction "2_2") (pintype "passive"))
      (node (ref "C27") (pin "2") (pinfunction "2_2") (pintype "passive"))
      (node (ref "C28") (pin "2") (pinfunction "2_2") (pintype "passive"))
      (node (ref "C5") (pin "2") (pinfunction "2_2") (pintype "passive"))
      (node (ref "U$11") (pin "8") (pinfunction "VCC_8") (pintype "bidirectional"))
      (node (ref "U$13") (pin "8") (pinfunction "VCC_8") (pintype "bidirectional"))
      (node (ref "U$17") (pin "P$29") (pinfunction "VREG5_P$29") (pintype "bidirectional"))
      (node (ref "U$4") (pin "8") (pinfunction "VCC_8") (pintype "bidirectional"))
      (node (ref "U$8") (pin "8") (pinfunction "VCC_8") (pintype "bidirectional"))
    )
    (net (code "5") (name "BAT-") (class "Default")
      (node (ref "BAT0") (pin "2") (pinfunction "1_2") (pintype "passive"))
      (node (ref "BAT1") (pin "2") (pinfunction "1_2") (pintype "passive"))
      (node (ref "BAT2") (pin "2") (pinfunction "1_2") (pintype "passive"))
      (node (ref "BAT3") (pin "2") (pinfunction "1_2") (pintype "passive"))
      (node (ref "U$27") (pin "P$4") (pinfunction "B_P$4") (pintype "bidirectional"))
      (node (ref "U$27") (pin "P$5") (pinfunction "B_P$5") (pintype "bidirectional"))
      (node (ref "U$27") (pin "P$6") (pinfunction "B_P$6") (pintype "bidirectional"))
    )
    (net (code "6") (name "BAT0_EN") (class "Default")
      (node (ref "Q5") (pin "1") (pinfunction "G_1") (pintype "bidirectional"))
      (node (ref "R48") (pin "2") (pinfunction "2_2") (pintype "passive"))
      (node (ref "X2") (pin "9") (pinfunction "KL_9") (pintype "passive"))
    )
    (net (code "7") (name "BAT0_G") (class "Default")
      (node (ref "C19") (pin "2") (pinfunction "2_2") (pintype "passive"))
      (node (ref "U$12") (pin "P$4") (pinfunction "G_P$4") (pintype "passive"))
      (node (ref "U$20") (pin "6") (pinfunction "GATE_6") (pintype "bidirectional"))
      (node (ref "U$5") (pin "P$4") (pinfunction "G_P$4") (pintype "passive"))
    )
    (net (code "8") (name "BAT0_S") (class "Default")
      (node (ref "C19") (pin "1") (pinfunction "1_1") (pintype "passive"))
      (node (ref "U$12") (pin "P$1") (pinfunction "S1_P$1") (pintype "passive"))
      (node (ref "U$12") (pin "P$2") (pinfunction "S2_P$2") (pintype "passive"))
      (node (ref "U$12") (pin "P$3") (pinfunction "S3_P$3") (pintype "passive"))
      (node (ref "U$20") (pin "7") (pinfunction "SRC_7") (pintype "bidirectional"))
      (node (ref "U$5") (pin "P$1") (pinfunction "S1_P$1") (pintype "passive"))
      (node (ref "U$5") (pin "P$2") (pinfunction "S2_P$2") (pintype "passive"))
      (node (ref "U$5") (pin "P$3") (pinfunction "S3_P$3") (pintype "passive"))
    )
    (net (code "9") (name "BAT1_EN") (class "Default")
      (node (ref "Q6") (pin "1") (pinfunction "G_1") (pintype "bidirectional"))
      (node (ref "R49") (pin "2") (pinfunction "2_2") (pintype "passive"))
      (node (ref "X2") (pin "11") (pinfunction "KL_11") (pintype "passive"))
    )
    (net (code "10") (name "BAT1_G") (class "Default")
      (node (ref "C12") (pin "2") (pinfunction "2_2") (pintype "passive"))
      (node (ref "U$10") (pin "P$4") (pinfunction "G_P$4") (pintype "passive"))
      (node (ref "U$22") (pin "6") (pinfunction "GATE_6") (pintype "bidirectional"))
      (node (ref "U$9") (pin "P$4") (pinfunction "G_P$4") (pintype "passive"))
    )
    (net (code "11") (name "BAT1_S") (class "Default")
      (node (ref "C12") (pin "1") (pinfunction "1_1") (pintype "passive"))
      (node (ref "U$10") (pin "P$1") (pinfunction "S1_P$1") (pintype "passive"))
      (node (ref "U$10") (pin "P$2") (pinfunction "S2_P$2") (pintype "passive"))
      (node (ref "U$10") (pin "P$3") (pinfunction "S3_P$3") (pintype "passive"))
      (node (ref "U$22") (pin "7") (pinfunction "SRC_7") (pintype "bidirectional"))
      (node (ref "U$9") (pin "P$1") (pinfunction "S1_P$1") (pintype "passive"))
      (node (ref "U$9") (pin "P$2") (pinfunction "S2_P$2") (pintype "passive"))
      (node (ref "U$9") (pin "P$3") (pinfunction "S3_P$3") (pintype "passive"))
    )
    (net (code "12") (name "BAT2_EN") (class "Default")
      (node (ref "Q7") (pin "1") (pinfunction "G_1") (pintype "bidirectional"))
      (node (ref "R50") (pin "2") (pinfunction "2_2") (pintype "passive"))
      (node (ref "X2") (pin "13") (pinfunction "KL_13") (pintype "passive"))
    )
    (net (code "13") (name "BAT2_G") (class "Default")
      (node (ref "C6") (pin "2") (pinfunction "2_2") (pintype "passive"))
      (node (ref "U$21") (pin "6") (pinfunction "GATE_6") (pintype "bidirectional"))
      (node (ref "U$6") (pin "P$4") (pinfunction "G_P$4") (pintype "passive"))
      (node (ref "U$7") (pin "P$4") (pinfunction "G_P$4") (pintype "passive"))
    )
    (net (code "14") (name "BAT2_S") (class "Default")
      (node (ref "C6") (pin "1") (pinfunction "1_1") (pintype "passive"))
      (node (ref "U$21") (pin "7") (pinfunction "SRC_7") (pintype "bidirectional"))
      (node (ref "U$6") (pin "P$1") (pinfunction "S1_P$1") (pintype "passive"))
      (node (ref "U$6") (pin "P$2") (pinfunction "S2_P$2") (pintype "passive"))
      (node (ref "U$6") (pin "P$3") (pinfunction "S3_P$3") (pintype "passive"))
      (node (ref "U$7") (pin "P$1") (pinfunction "S1_P$1") (pintype "passive"))
      (node (ref "U$7") (pin "P$2") (pinfunction "S2_P$2") (pintype "passive"))
      (node (ref "U$7") (pin "P$3") (pinfunction "S3_P$3") (pintype "passive"))
    )
    (net (code "15") (name "BAT3_EN") (class "Default")
      (node (ref "Q8") (pin "1") (pinfunction "G_1") (pintype "bidirectional"))
      (node (ref "R51") (pin "2") (pinfunction "2_2") (pintype "passive"))
      (node (ref "X2") (pin "15") (pinfunction "KL_15") (pintype "passive"))
    )
    (net (code "16") (name "BAT3_G") (class "Default")
      (node (ref "C9") (pin "2") (pinfunction "2_2") (pintype "passive"))
      (node (ref "U$2") (pin "P$4") (pinfunction "G_P$4") (pintype "passive"))
      (node (ref "U$23") (pin "6") (pinfunction "GATE_6") (pintype "bidirectional"))
      (node (ref "U$3") (pin "P$4") (pinfunction "G_P$4") (pintype "passive"))
    )
    (net (code "17") (name "BAT3_S") (class "Default")
      (node (ref "C9") (pin "1") (pinfunction "1_1") (pintype "passive"))
      (node (ref "U$2") (pin "P$1") (pinfunction "S1_P$1") (pintype "passive"))
      (node (ref "U$2") (pin "P$2") (pinfunction "S2_P$2") (pintype "passive"))
      (node (ref "U$2") (pin "P$3") (pinfunction "S3_P$3") (pintype "passive"))
      (node (ref "U$23") (pin "7") (pinfunction "SRC_7") (pintype "bidirectional"))
      (node (ref "U$3") (pin "P$1") (pinfunction "S1_P$1") (pintype "passive"))
      (node (ref "U$3") (pin "P$2") (pinfunction "S2_P$2") (pintype "passive"))
      (node (ref "U$3") (pin "P$3") (pinfunction "S3_P$3") (pintype "passive"))
    )
    (net (code "18") (name "COMP1") (class "Default")
      (node (ref "C34") (pin "1") (pinfunction "1_1") (pintype "passive"))
      (node (ref "R23") (pin "1") (pinfunction "1_1") (pintype "passive"))
      (node (ref "U$17") (pin "P$10") (pinfunction "COMP1_P$10") (pintype "bidirectional"))
    )
    (net (code "19") (name "COMP2") (class "Default")
      (node (ref "C33") (pin "1") (pinfunction "1_1") (pintype "passive"))
      (node (ref "R39") (pin "2") (pinfunction "2_2") (pintype "passive"))
      (node (ref "U$17") (pin "P$15") (pinfunction "COMP2_P$15") (pintype "bidirectional"))
    )
    (net (code "20") (name "COMPUTER_PWR") (class "Default")
      (node (ref "X2") (pin "28") (pinfunction "KL_28") (pintype "passive"))
      (node (ref "X5") (pin "2") (pinfunction "S_2") (pintype "passive"))
    )
    (net (code "21") (name "CSN1") (class "Default")
      (node (ref "C16") (pin "1") (pinfunction "1_1") (pintype "passive"))
      (node (ref "R21") (pin "2") (pinfunction "2_2") (pintype "passive"))
      (node (ref "R25") (pin "2") (pinfunction "2_2") (pintype "passive"))
      (node (ref "SJ114") (pin "1") (pinfunction "1_1") (pintype "passive"))
      (node (ref "U$17") (pin "P$2") (pinfunction "V5SW_P$2") (pintype "bidirectional"))
      (node (ref "U$17") (pin "P$8") (pinfunction "CSN1_P$8") (pintype "bidirectional"))
    )
    (net (code "22") (name "CSN2") (class "Default")
      (node (ref "C20") (pin "1") (pinfunction "1_1") (pintype "passive"))
      (node (ref "R33") (pin "1") (pinfunction "1_1") (pintype "passive"))
      (node (ref "R40") (pin "2") (pinfunction "2_2") (pintype "passive"))
      (node (ref "SJ100") (pin "1") (pinfunction "1_1") (pintype "passive"))
      (node (ref "U$17") (pin "P$17") (pinfunction "CSN2_P$17") (pintype "bidirectional"))
    )
    (net (code "23") (name "CSP1") (class "Default")
      (node (ref "C16") (pin "2") (pinfunction "2_2") (pintype "passive"))
      (node (ref "R25") (pin "1") (pinfunction "1_1") (pintype "passive"))
      (node (ref "R31") (pin "1") (pinfunction "1_1") (pintype "passive"))
      (node (ref "U$17") (pin "P$7") (pinfunction "CSP1_P$7") (pintype "bidirectional"))
    )
    (net (code "24") (name "CSP2") (class "Default")
      (node (ref "C20") (pin "2") (pinfunction "2_2") (pintype "passive"))
      (node (ref "R32") (pin "1") (pinfunction "1_1") (pintype "passive"))
      (node (ref "R33") (pin "2") (pinfunction "2_2") (pintype "passive"))
      (node (ref "U$17") (pin "P$18") (pinfunction "CSP2_P$18") (pintype "bidirectional"))
    )
    (net (code "25") (name "DRVH1") (class "Default")
      (node (ref "U$105") (pin "4") (pinfunction "G_4") (pintype "passive"))
      (node (ref "U$17") (pin "P$1") (pinfunction "DRVH1_P$1") (pintype "bidirectional"))
    )
    (net (code "26") (name "DRVH2") (class "Default")
      (node (ref "U$108") (pin "4") (pinfunction "G_4") (pintype "passive"))
      (node (ref "U$17") (pin "P$24") (pinfunction "DRVH2_P$24") (pintype "bidirectional"))
    )
    (net (code "27") (name "DRVL1") (class "Default")
      (node (ref "U$106") (pin "4") (pinfunction "G_4") (pintype "passive"))
      (node (ref "U$17") (pin "P$30") (pinfunction "DRVL1_P$30") (pintype "bidirectional"))
    )
    (net (code "28") (name "DRVL2") (class "Default")
      (node (ref "U$107") (pin "4") (pinfunction "G_4") (pintype "passive"))
      (node (ref "U$17") (pin "P$27") (pinfunction "DRVL2_P$27") (pintype "bidirectional"))
    )
    (net (code "29") (name "ENABLE_PWR") (class "Default")
      (node (ref "U$17") (pin "P$12") (pinfunction "EN_P$12") (pintype "bidirectional"))
      (node (ref "X2") (pin "30") (pinfunction "KL_30") (pintype "passive"))
    )
    (net (code "30") (name "GND") (class "Default")
      (node (ref "19V") (pin "1") (pinfunction "1_1") (pintype "passive"))
      (node (ref "C1") (pin "-") (pinfunction "-_-") (pintype "passive"))
      (node (ref "C10") (pin "2") (pinfunction "2_2") (pintype "passive"))
      (node (ref "C104") (pin "2") (pinfunction "2_2") (pintype "passive"))
      (node (ref "C11") (pin "1") (pinfunction "1_1") (pintype "passive"))
      (node (ref "C113") (pin "2") (pinfunction "2_2") (pintype "passive"))
      (node (ref "C13") (pin "-") (pinfunction "-_-") (pintype "passive"))
      (node (ref "C14") (pin "-") (pinfunction "-_-") (pintype "passive"))
      (node (ref "C15") (pin "-") (pinfunction "-_-") (pintype "passive"))
      (node (ref "C17") (pin "1") (pinfunction "1_1") (pintype "passive"))
      (node (ref "C18") (pin "1") (pinfunction "1_1") (pintype "passive"))
      (node (ref "C2") (pin "-") (pinfunction "-_-") (pintype "passive"))
      (node (ref "C25") (pin "1") (pinfunction "1_1") (pintype "passive"))
      (node (ref "C26") (pin "1") (pinfunction "1_1") (pintype "passive"))
      (node (ref "C27") (pin "1") (pinfunction "1_1") (pintype "passive"))
      (node (ref "C28") (pin "1") (pinfunction "1_1") (pintype "passive"))
      (node (ref "C29") (pin "1") (pinfunction "1_1") (pintype "passive"))
      (node (ref "C3") (pin "-") (pinfunction "-_-") (pintype "passive"))
      (node (ref "C30") (pin "-") (pinfunction "-_-") (pintype "passive"))
      (node (ref "C31") (pin "-") (pinfunction "-_-") (pintype "passive"))
      (node (ref "C32") (pin "2") (pinfunction "2_2") (pintype "passive"))
      (node (ref "C35") (pin "-") (pinfunction "-_-") (pintype "passive"))
      (node (ref "C36") (pin "-") (pinfunction "-_-") (pintype "passive"))
      (node (ref "C37") (pin "-") (pinfunction "-_-") (pintype "passive"))
      (node (ref "C38") (pin "-") (pinfunction "-_-") (pintype "passive"))
      (node (ref "C39") (pin "-") (pinfunction "-_-") (pintype "passive"))
      (node (ref "C4") (pin "1") (pinfunction "1_1") (pintype "passive"))
      (node (ref "C40") (pin "2") (pinfunction "2_2") (pintype "passive"))
      (node (ref "C41") (pin "2") (pinfunction "2_2") (pintype "passive"))
      (node (ref "C42") (pin "2") (pinfunction "2_2") (pintype "passive"))
      (node (ref "C43") (pin "2") (pinfunction "2_2") (pintype "passive"))
      (node (ref "C44") (pin "-") (pinfunction "-_-") (pintype "passive"))
      (node (ref "C45") (pin "-") (pinfunction "-_-") (pintype "passive"))
      (node (ref "C5") (pin "1") (pinfunction "1_1") (pintype "passive"))
      (node (ref "C7") (pin "1") (pinfunction "1_1") (pintype "passive"))
      (node (ref "D2") (pin "A") (pinfunction "A_A") (pintype "passive"))
      (node (ref "D20") (pin "A") (pinfunction "A_A") (pintype "passive"))
      (node (ref "D21") (pin "A") (pinfunction "A_A") (pintype "passive"))
      (node (ref "D22") (pin "A") (pinfunction "A_A") (pintype "passive"))
      (node (ref "D23") (pin "A") (pinfunction "A_A") (pintype "passive"))
      (node (ref "M1") (pin "2") (pinfunction "1_2") (pintype "passive"))
      (node (ref "M2") (pin "2") (pinfunction "1_2") (pintype "passive"))
      (node (ref "M3") (pin "2") (pinfunction "1_2") (pintype "passive"))
      (node (ref "M4") (pin "2") (pinfunction "1_2") (pintype "passive"))
      (node (ref "MISC") (pin "2") (pinfunction "1_2") (pintype "passive"))
      (node (ref "PC") (pin "2") (pinfunction "1_2") (pintype "passive"))
      (node (ref "PWRLED") (pin "C") (pinfunction "C_C") (pintype "passive"))
      (node (ref "Q1") (pin "2") (pinfunction "S_2") (pintype "bidirectional"))
      (node (ref "Q2") (pin "2") (pinfunction "S_2") (pintype "bidirectional"))
      (node (ref "Q3") (pin "2") (pinfunction "S_2") (pintype "bidirectional"))
      (node (ref "Q4") (pin "2") (pinfunction "S_2") (pintype "bidirectional"))
      (node (ref "Q5") (pin "2") (pinfunction "S_2") (pintype "bidirectional"))
      (node (ref "Q6") (pin "2") (pinfunction "S_2") (pintype "bidirectional"))
      (node (ref "Q7") (pin "2") (pinfunction "S_2") (pintype "bidirectional"))
      (node (ref "Q8") (pin "2") (pinfunction "S_2") (pintype "bidirectional"))
      (node (ref "R1") (pin "1") (pinfunction "1_1") (pintype "passive"))
      (node (ref "R13") (pin "1") (pinfunction "1_1") (pintype "passive"))
      (node (ref "R16") (pin "1") (pinfunction "1_1") (pintype "passive"))
      (node (ref "R18") (pin "1") (pinfunction "1_1") (pintype "passive"))
      (node (ref "R2") (pin "1") (pinfunction "1_1") (pintype "passive"))
      (node (ref "R20") (pin "1") (pinfunction "1_1") (pintype "passive"))
      (node (ref "R22") (pin "1") (pinfunction "1_1") (pintype "passive"))
      (node (ref "R24") (pin "1") (pinfunction "1_1") (pintype "passive"))
      (node (ref "R26") (pin "1") (pinfunction "1_1") (pintype "passive"))
      (node (ref "R28") (pin "1") (pinfunction "1_1") (pintype "passive"))
      (node (ref "R29") (pin "1") (pinfunction "1_1") (pintype "passive"))
      (node (ref "R3") (pin "1") (pinfunction "1_1") (pintype "passive"))
      (node (ref "R35") (pin "1") (pinfunction "1_1") (pintype "passive"))
      (node (ref "R36") (pin "1") (pinfunction "1_1") (pintype "passive"))
      (node (ref "R4") (pin "1") (pinfunction "1_1") (pintype "passive"))
      (node (ref "R41") (pin "1") (pinfunction "1_1") (pintype "passive"))
      (node (ref "R42") (pin "1") (pinfunction "1_1") (pintype "passive"))
      (node (ref "R45") (pin "1") (pinfunction "1_1") (pintype "passive"))
      (node (ref "R46") (pin "1") (pinfunction "1_1") (pintype "passive"))
      (node (ref "R48") (pin "1") (pinfunction "1_1") (pintype "passive"))
      (node (ref "R49") (pin "1") (pinfunction "1_1") (pintype "passive"))
      (node (ref "R5") (pin "1") (pinfunction "1_1") (pintype "passive"))
      (node (ref "R50") (pin "1") (pinfunction "1_1") (pintype "passive"))
      (node (ref "R51") (pin "1") (pinfunction "1_1") (pintype "passive"))
      (node (ref "R6") (pin "1") (pinfunction "1_1") (pintype "passive"))
      (node (ref "R7") (pin "1") (pinfunction "1_1") (pintype "passive"))
      (node (ref "R8") (pin "1") (pinfunction "1_1") (pintype "passive"))
      (node (ref "R9") (pin "1") (pinfunction "1_1") (pintype "passive"))
      (node (ref "U$106") (pin "1") (pinfunction "S_1") (pintype "passive"))
      (node (ref "U$106") (pin "2") (pinfunction "S_2") (pintype "passive"))
      (node (ref "U$106") (pin "3") (pinfunction "S_3") (pintype "passive"))
      (node (ref "U$107") (pin "1") (pinfunction "S_1") (pintype "passive"))
      (node (ref "U$107") (pin "2") (pinfunction "S_2") (pintype "passive"))
      (node (ref "U$107") (pin "3") (pinfunction "S_3") (pintype "passive"))
      (node (ref "U$11") (pin "5") (pinfunction "GND_5") (pintype "bidirectional"))
      (node (ref "U$13") (pin "5") (pinfunction "GND_5") (pintype "bidirectional"))
      (node (ref "U$17") (pin "P$28") (pinfunction "GND_P$28") (pintype "bidirectional"))
      (node (ref "U$17") (pin "P$33") (pinfunction "TAB_P$33") (pintype "bidirectional"))
      (node (ref "U$20") (pin "5") (pinfunction "GND_5") (pintype "bidirectional"))
      (node (ref "U$21") (pin "5") (pinfunction "GND_5") (pintype "bidirectional"))
      (node (ref "U$22") (pin "5") (pinfunction "GND_5") (pintype "bidirectional"))
      (node (ref "U$23") (pin "5") (pinfunction "GND_5") (pintype "bidirectional"))
      (node (ref "U$24") (pin "1") (pinfunction "~{ON}_1") (pintype "bidirectional"))
      (node (ref "U$24") (pin "4") (pinfunction "LBI_4") (pintype "bidirectional"))
      (node (ref "U$24") (pin "5") (pinfunction "GND_5") (pintype "bidirectional"))
      (node (ref "U$25") (pin "1") (pinfunction "~{ON}_1") (pintype "bidirectional"))
      (node (ref "U$25") (pin "4") (pinfunction "LBI_4") (pintype "bidirectional"))
      (node (ref "U$25") (pin "5") (pinfunction "GND_5") (pintype "bidirectional"))
      (node (ref "U$26") (pin "1") (pinfunction "~{ON}_1") (pintype "bidirectional"))
      (node (ref "U$26") (pin "4") (pinfunction "LBI_4") (pintype "bidirectional"))
      (node (ref "U$26") (pin "5") (pinfunction "GND_5") (pintype "bidirectional"))
      (node (ref "U$27") (pin "P$1") (pinfunction "A_P$1") (pintype "bidirectional"))
      (node (ref "U$27") (pin "P$2") (pinfunction "A_P$2") (pintype "bidirectional"))
      (node (ref "U$27") (pin "P$3") (pinfunction "A_P$3") (pintype "bidirectional"))
      (node (ref "U$4") (pin "5") (pinfunction "GND_5") (pintype "bidirectional"))
      (node (ref "U$8") (pin "5") (pinfunction "GND_5") (pintype "bidirectional"))
      (node (ref "X1") (pin "2") (pinfunction "1_2") (pintype "passive"))
      (node (ref "X1") (pin "4") (pinfunction "1_4") (pintype "passive"))
      (node (ref "X2") (pin "10") (pinfunction "KL_10") (pintype "passive"))
      (node (ref "X2") (pin "17") (pinfunction "KL_17") (pintype "passive"))
      (node (ref "X3") (pin "1") (pinfunction "S_1") (pintype "passive"))
      (node (ref "X4") (pin "1") (pinfunction "S_1") (pintype "passive"))
      (node (ref "X5") (pin "1") (pinfunction "S_1") (pintype "passive"))
    )
    (net (code "31") (name "IBAT0_AD") (class "Default")
      (node (ref "U$13") (pin "7") (pinfunction "VOUT_7") (pintype "bidirectional"))
      (node (ref "X2") (pin "19") (pinfunction "KL_19") (pintype "passive"))
    )
    (net (code "32") (name "IBAT1_AD") (class "Default")
      (node (ref "U$11") (pin "7") (pinfunction "VOUT_7") (pintype "bidirectional"))
      (node (ref "X2") (pin "21") (pinfunction "KL_21") (pintype "passive"))
    )
    (net (code "33") (name "IBAT2_AD") (class "Default")
      (node (ref "U$8") (pin "7") (pinfunction "VOUT_7") (pintype "bidirectional"))
      (node (ref "X2") (pin "23") (pinfunction "KL_23") (pintype "passive"))
    )
    (net (code "34") (name "IBAT3_AD") (class "Default")
      (node (ref "U$4") (pin "7") (pinfunction "VOUT_7") (pintype "bidirectional"))
      (node (ref "X2") (pin "25") (pinfunction "KL_25") (pintype "passive"))
    )
    (net (code "35") (name "IMON1") (class "Default")
      (node (ref "U$17") (pin "P$11") (pinfunction "IMON1_P$11") (pintype "bidirectional"))
      (node (ref "X2") (pin "27") (pinfunction "KL_27") (pintype "passive"))
    )
    (net (code "36") (name "IMON2") (class "Default")
      (node (ref "U$17") (pin "P$14") (pinfunction "IMON2_P$14") (pintype "bidirectional"))
      (node (ref "X2") (pin "29") (pinfunction "KL_29") (pintype "passive"))
    )
    (net (code "37") (name "LBI0") (class "Default")
      (node (ref "C40") (pin "1") (pinfunction "1_1") (pintype "passive"))
      (node (ref "R11") (pin "1") (pinfunction "1_1") (pintype "passive"))
      (node (ref "R13") (pin "2") (pinfunction "2_2") (pintype "passive"))
      (node (ref "U$20") (pin "4") (pinfunction "LBI_4") (pintype "bidirectional"))
    )
    (net (code "38") (name "LBI1") (class "Default")
      (node (ref "C41") (pin "1") (pinfunction "1_1") (pintype "passive"))
      (node (ref "R15") (pin "1") (pinfunction "1_1") (pintype "passive"))
      (node (ref "R16") (pin "2") (pinfunction "2_2") (pintype "passive"))
      (node (ref "U$22") (pin "4") (pinfunction "LBI_4") (pintype "bidirectional"))
    )
    (net (code "39") (name "LBI2") (class "Default")
      (node (ref "C42") (pin "1") (pinfunction "1_1") (pintype "passive"))
      (node (ref "R17") (pin "1") (pinfunction "1_1") (pintype "passive"))
      (node (ref "R18") (pin "2") (pinfunction "2_2") (pintype "passive"))
      (node (ref "U$21") (pin "4") (pinfunction "LBI_4") (pintype "bidirectional"))
    )
    (net (code "40") (name "LBI3") (class "Default")
      (node (ref "C43") (pin "1") (pinfunction "1_1") (pintype "passive"))
      (node (ref "R19") (pin "1") (pinfunction "1_1") (pintype "passive"))
      (node (ref "R20") (pin "2") (pinfunction "2_2") (pintype "passive"))
      (node (ref "U$23") (pin "4") (pinfunction "LBI_4") (pintype "bidirectional"))
    )
    (net (code "41") (name "Net-(BAT0-Pad1)") (class "Default")
      (node (ref "BAT0") (pin "1") (pinfunction "1_1") (pintype "passive"))
      (node (ref "F3") (pin "2") (pinfunction "2_2") (pintype "bidirectional"))
    )
    (net (code "42") (name "Net-(BAT1-Pad1)") (class "Default")
      (node (ref "BAT1") (pin "1") (pinfunction "1_1") (pintype "passive"))
      (node (ref "F4") (pin "2") (pinfunction "2_2") (pintype "bidirectional"))
    )
    (net (code "43") (name "Net-(BAT2-Pad1)") (class "Default")
      (node (ref "BAT2") (pin "1") (pinfunction "1_1") (pintype "passive"))
      (node (ref "F5") (pin "2") (pinfunction "2_2") (pintype "bidirectional"))
    )
    (net (code "44") (name "Net-(BAT3-Pad1)") (class "Default")
      (node (ref "BAT3") (pin "1") (pinfunction "1_1") (pintype "passive"))
      (node (ref "F6") (pin "2") (pinfunction "2_2") (pintype "bidirectional"))
    )
    (net (code "45") (name "Net-(D2-PadC)") (class "Default")
      (node (ref "D2") (pin "C") (pinfunction "C_C") (pintype "passive"))
      (node (ref "F7") (pin "2") (pinfunction "2_2") (pintype "bidirectional"))
      (node (ref "LED1") (pin "A") (pinfunction "A_A") (pintype "passive"))
      (node (ref "M1") (pin "1") (pinfunction "1_1") (pintype "passive"))
    )
    (net (code "46") (name "Net-(D21-PadC)") (class "Default")
      (node (ref "D21") (pin "C") (pinfunction "C_C") (pintype "passive"))
      (node (ref "F8") (pin "2") (pinfunction "2_2") (pintype "bidirectional"))
      (node (ref "LED2") (pin "A") (pinfunction "A_A") (pintype "passive"))
      (node (ref "M2") (pin "1") (pinfunction "1_1") (pintype "passive"))
    )
    (net (code "47") (name "Net-(D22-PadC)") (class "Default")
      (node (ref "D22") (pin "C") (pinfunction "C_C") (pintype "passive"))
      (node (ref "F9") (pin "2") (pinfunction "2_2") (pintype "bidirectional"))
      (node (ref "LED3") (pin "A") (pinfunction "A_A") (pintype "passive"))
      (node (ref "M3") (pin "1") (pinfunction "1_1") (pintype "passive"))
    )
    (net (code "48") (name "Net-(D23-PadC)") (class "Default")
      (node (ref "D23") (pin "C") (pinfunction "C_C") (pintype "passive"))
      (node (ref "F10") (pin "2") (pinfunction "2_2") (pintype "bidirectional"))
      (node (ref "LED4") (pin "A") (pinfunction "A_A") (pintype "passive"))
      (node (ref "M4") (pin "1") (pinfunction "1_1") (pintype "passive"))
    )
    (net (code "49") (name "Net-(F1-Pad2)") (class "Default")
      (node (ref "F1") (pin "2") (pinfunction "2_2") (pintype "bidirectional"))
      (node (ref "LED5") (pin "A") (pinfunction "A_A") (pintype "passive"))
      (node (ref "PC") (pin "1") (pinfunction "1_1") (pintype "passive"))
    )
    (net (code "50") (name "Net-(F2-Pad2)") (class "Default")
      (node (ref "F2") (pin "2") (pinfunction "2_2") (pintype "bidirectional"))
      (node (ref "LED6") (pin "A") (pinfunction "A_A") (pintype "passive"))
      (node (ref "MISC") (pin "1") (pinfunction "1_1") (pintype "passive"))
    )
    (net (code "51") (name "Net-(LED1-PadC)") (class "Default")
      (node (ref "LED1") (pin "C") (pinfunction "C_C") (pintype "passive"))
      (node (ref "R6") (pin "2") (pinfunction "2_2") (pintype "passive"))
    )
    (net (code "52") (name "Net-(LED2-PadC)") (class "Default")
      (node (ref "LED2") (pin "C") (pinfunction "C_C") (pintype "passive"))
      (node (ref "R7") (pin "2") (pinfunction "2_2") (pintype "passive"))
    )
    (net (code "53") (name "Net-(LED3-PadC)") (class "Default")
      (node (ref "LED3") (pin "C") (pinfunction "C_C") (pintype "passive"))
      (node (ref "R8") (pin "2") (pinfunction "2_2") (pintype "passive"))
    )
    (net (code "54") (name "Net-(LED4-PadC)") (class "Default")
      (node (ref "LED4") (pin "C") (pinfunction "C_C") (pintype "passive"))
      (node (ref "R9") (pin "2") (pinfunction "2_2") (pintype "passive"))
    )
    (net (code "55") (name "Net-(LED5-PadC)") (class "Default")
      (node (ref "LED5") (pin "C") (pinfunction "C_C") (pintype "passive"))
      (node (ref "R1") (pin "2") (pinfunction "2_2") (pintype "passive"))
    )
    (net (code "56") (name "Net-(LED6-PadC)") (class "Default")
      (node (ref "LED6") (pin "C") (pinfunction "C_C") (pintype "passive"))
      (node (ref "R2") (pin "2") (pinfunction "2_2") (pintype "passive"))
    )
    (net (code "57") (name "Net-(PWRLED-PadA)") (class "Default")
      (node (ref "PWRLED") (pin "A") (pinfunction "A_A") (pintype "passive"))
      (node (ref "R12") (pin "1") (pinfunction "1_1") (pintype "passive"))
    )
    (net (code "58") (name "Net-(U$4-FILT)") (class "Default")
      (node (ref "C7") (pin "2") (pinfunction "2_2") (pintype "passive"))
      (node (ref "U$4") (pin "6") (pinfunction "FILT_6") (pintype "bidirectional"))
    )
    (net (code "59") (name "Net-(U$8-FILT)") (class "Default")
      (node (ref "C4") (pin "2") (pinfunction "2_2") (pintype "passive"))
      (node (ref "U$8") (pin "6") (pinfunction "FILT_6") (pintype "bidirectional"))
    )
    (net (code "60") (name "Net-(U$11-FILT)") (class "Default")
      (node (ref "C11") (pin "2") (pinfunction "2_2") (pintype "passive"))
      (node (ref "U$11") (pin "6") (pinfunction "FILT_6") (pintype "bidirectional"))
    )
    (net (code "61") (name "Net-(U$13-FILT)") (class "Default")
      (node (ref "C18") (pin "2") (pinfunction "2_2") (pintype "passive"))
      (node (ref "U$13") (pin "6") (pinfunction "FILT_6") (pintype "bidirectional"))
    )
    (net (code "62") (name "Net-(U$17-RF)") (class "Default")
      (node (ref "R3") (pin "2") (pinfunction "2_2") (pintype "passive"))
      (node (ref "U$17") (pin "P$3") (pinfunction "RF_P$3") (pintype "bidirectional"))
    )
    (net (code "63") (name "Net-(U$17-VBST)") (class "Default")
      (node (ref "C21") (pin "1") (pinfunction "1_1") (pintype "passive"))
      (node (ref "U$17") (pin "P$26") (pinfunction "VBST_P$26") (pintype "bidirectional"))
    )
    (net (code "64") (name "Net-(U$17-VBST1)") (class "Default")
      (node (ref "C8") (pin "1") (pinfunction "1_1") (pintype "passive"))
      (node (ref "U$17") (pin "P$31") (pinfunction "VBST1_P$31") (pintype "bidirectional"))
    )
    (net (code "65") (name "Net-(U$17-VFB1)") (class "Default")
      (node (ref "R21") (pin "1") (pinfunction "1_1") (pintype "passive"))
      (node (ref "R4") (pin "2") (pinfunction "2_2") (pintype "passive"))
      (node (ref "U$17") (pin "P$9") (pinfunction "VFB1_P$9") (pintype "bidirectional"))
    )
    (net (code "66") (name "Net-(U$17-VFB2)") (class "Default")
      (node (ref "R40") (pin "1") (pinfunction "1_1") (pintype "passive"))
      (node (ref "R5") (pin "2") (pinfunction "2_2") (pintype "passive"))
      (node (ref "U$17") (pin "P$16") (pinfunction "VFB2_P$16") (pintype "bidirectional"))
    )
    (net (code "67") (name "OUT1_EN") (class "Default")
      (node (ref "R26") (pin "2") (pinfunction "2_2") (pintype "passive"))
      (node (ref "U$24") (pin "2") (pinfunction "~{OFF}_2") (pintype "bidirectional"))
      (node (ref "X2") (pin "18") (pinfunction "KL_18") (pintype "passive"))
    )
    (net (code "68") (name "OUT1_G") (class "Default")
      (node (ref "C24") (pin "2") (pinfunction "2_2") (pintype "passive"))
      (node (ref "U$1") (pin "P$4") (pinfunction "G_P$4") (pintype "passive"))
      (node (ref "U$24") (pin "6") (pinfunction "GATE_6") (pintype "bidirectional"))
    )
    (net (code "69") (name "OUT1_S") (class "Default")
      (node (ref "C24") (pin "1") (pinfunction "1_1") (pintype "passive"))
      (node (ref "F10") (pin "1") (pinfunction "1_1") (pintype "bidirectional"))
      (node (ref "F7") (pin "1") (pinfunction "1_1") (pintype "bidirectional"))
      (node (ref "F8") (pin "1") (pinfunction "1_1") (pintype "bidirectional"))
      (node (ref "F9") (pin "1") (pinfunction "1_1") (pintype "bidirectional"))
      (node (ref "U$1") (pin "P$1") (pinfunction "S1_P$1") (pintype "passive"))
      (node (ref "U$1") (pin "P$2") (pinfunction "S2_P$2") (pintype "passive"))
      (node (ref "U$1") (pin "P$3") (pinfunction "S3_P$3") (pintype "passive"))
      (node (ref "U$24") (pin "7") (pinfunction "SRC_7") (pintype "bidirectional"))
    )
    (net (code "70") (name "OUT2_EN") (class "Default")
      (node (ref "R24") (pin "2") (pinfunction "2_2") (pintype "passive"))
      (node (ref "U$25") (pin "2") (pinfunction "~{OFF}_2") (pintype "bidirectional"))
      (node (ref "X2") (pin "20") (pinfunction "KL_20") (pintype "passive"))
    )
    (net (code "71") (name "OUT2_G") (class "Default")
      (node (ref "C22") (pin "2") (pinfunction "2_2") (pintype "passive"))
      (node (ref "U$14") (pin "P$4") (pinfunction "G_P$4") (pintype "passive"))
      (node (ref "U$25") (pin "6") (pinfunction "GATE_6") (pintype "bidirectional"))
    )
    (net (code "72") (name "OUT2_S") (class "Default")
      (node (ref "C22") (pin "1") (pinfunction "1_1") (pintype "passive"))
      (node (ref "F1") (pin "1") (pinfunction "1_1") (pintype "bidirectional"))
      (node (ref "U$14") (pin "P$1") (pinfunction "S1_P$1") (pintype "passive"))
      (node (ref "U$14") (pin "P$2") (pinfunction "S2_P$2") (pintype "passive"))
      (node (ref "U$14") (pin "P$3") (pinfunction "S3_P$3") (pintype "passive"))
      (node (ref "U$25") (pin "7") (pinfunction "SRC_7") (pintype "bidirectional"))
    )
    (net (code "73") (name "OUT3_EN") (class "Default")
      (node (ref "R22") (pin "2") (pinfunction "2_2") (pintype "passive"))
      (node (ref "U$26") (pin "2") (pinfunction "~{OFF}_2") (pintype "bidirectional"))
      (node (ref "X2") (pin "22") (pinfunction "KL_22") (pintype "passive"))
    )
    (net (code "74") (name "OUT3_G") (class "Default")
      (node (ref "C23") (pin "2") (pinfunction "2_2") (pintype "passive"))
      (node (ref "U$15") (pin "P$4") (pinfunction "G_P$4") (pintype "passive"))
      (node (ref "U$26") (pin "6") (pinfunction "GATE_6") (pintype "bidirectional"))
    )
    (net (code "75") (name "OUT3_S") (class "Default")
      (node (ref "C23") (pin "1") (pinfunction "1_1") (pintype "passive"))
      (node (ref "F2") (pin "1") (pinfunction "1_1") (pintype "bidirectional"))
      (node (ref "U$15") (pin "P$1") (pinfunction "S1_P$1") (pintype "passive"))
      (node (ref "U$15") (pin "P$2") (pinfunction "S2_P$2") (pintype "passive"))
      (node (ref "U$15") (pin "P$3") (pinfunction "S3_P$3") (pintype "passive"))
      (node (ref "U$26") (pin "7") (pinfunction "SRC_7") (pintype "bidirectional"))
    )
    (net (code "76") (name "OUT4_EN") (class "Default")
      (node (ref "U$17") (pin "P$4") (pinfunction "EN1_P$4") (pintype "bidirectional"))
      (node (ref "X2") (pin "24") (pinfunction "KL_24") (pintype "passive"))
    )
    (net (code "77") (name "OUT5_EN") (class "Default")
      (node (ref "U$17") (pin "P$21") (pinfunction "EN2_P$21") (pintype "bidirectional"))
      (node (ref "X2") (pin "26") (pinfunction "KL_26") (pintype "passive"))
    )
    (net (code "78") (name "PGOOD1") (class "Default")
      (node (ref "R10") (pin "2") (pinfunction "2_2") (pintype "passive"))
      (node (ref "U$17") (pin "P$5") (pinfunction "PGOOD1_P$5") (pintype "bidirectional"))
      (node (ref "X2") (pin "31") (pinfunction "KL_31") (pintype "passive"))
    )
    (net (code "79") (name "PGOOD2") (class "Default")
      (node (ref "R14") (pin "2") (pinfunction "2_2") (pintype "passive"))
      (node (ref "U$17") (pin "P$20") (pinfunction "PGOOD2_P$20") (pintype "bidirectional"))
      (node (ref "X2") (pin "33") (pinfunction "KL_33") (pintype "passive"))
    )
    (net (code "80") (name "PWM_A") (class "Default")
      (node (ref "X2") (pin "34") (pinfunction "KL_34") (pintype "passive"))
      (node (ref "X3") (pin "3") (pinfunction "S_3") (pintype "passive"))
    )
    (net (code "81") (name "PWM_B") (class "Default")
      (node (ref "X2") (pin "32") (pinfunction "KL_32") (pintype "passive"))
      (node (ref "X4") (pin "3") (pinfunction "S_3") (pintype "passive"))
    )
    (net (code "82") (name "SERVO") (class "Default")
      (node (ref "C104") (pin "1") (pinfunction "1_1") (pintype "passive"))
      (node (ref "C15") (pin "+") (pinfunction "+_+") (pintype "passive"))
      (node (ref "C2") (pin "+") (pinfunction "+_+") (pintype "passive"))
      (node (ref "C30") (pin "+") (pinfunction "+_+") (pintype "passive"))
      (node (ref "L2") (pin "2") (pinfunction "2_2") (pintype "passive"))
      (node (ref "SJ100") (pin "2") (pinfunction "2_2") (pintype "passive"))
      (node (ref "X1") (pin "3") (pinfunction "1_3") (pintype "passive"))
      (node (ref "X3") (pin "2") (pinfunction "S_2") (pintype "passive"))
      (node (ref "X4") (pin "2") (pinfunction "S_2") (pintype "passive"))
    )
    (net (code "83") (name "SW1") (class "Default")
      (node (ref "C8") (pin "2") (pinfunction "2_2") (pintype "passive"))
      (node (ref "R31") (pin "2") (pinfunction "2_2") (pintype "passive"))
      (node (ref "SJ108") (pin "1") (pinfunction "1_1") (pintype "passive"))
      (node (ref "U$17") (pin "P$32") (pinfunction "SW1_P$32") (pintype "bidirectional"))
    )
    (net (code "84") (name "SW2") (class "Default")
      (node (ref "C21") (pin "2") (pinfunction "2_2") (pintype "passive"))
      (node (ref "R32") (pin "2") (pinfunction "2_2") (pintype "passive"))
      (node (ref "SJ110") (pin "1") (pinfunction "1_1") (pintype "passive"))
      (node (ref "U$17") (pin "P$25") (pinfunction "SW2_P$25") (pintype "bidirectional"))
    )
    (net (code "85") (name "V+") (class "Default")
      (node (ref "C13") (pin "+") (pinfunction "+_+") (pintype "passive"))
      (node (ref "C14") (pin "+") (pinfunction "+_+") (pintype "passive"))
      (node (ref "C29") (pin "2") (pinfunction "2_2") (pintype "passive"))
      (node (ref "C3") (pin "+") (pinfunction "+_+") (pintype "passive"))
      (node (ref "C32") (pin "1") (pinfunction "1_1") (pintype "passive"))
      (node (ref "C36") (pin "+") (pinfunction "+_+") (pintype "passive"))
      (node (ref "C37") (pin "+") (pinfunction "+_+") (pintype "passive"))
      (node (ref "C38") (pin "+") (pinfunction "+_+") (pintype "passive"))
      (node (ref "C39") (pin "+") (pinfunction "+_+") (pintype "passive"))
      (node (ref "C44") (pin "+") (pinfunction "+_+") (pintype "passive"))
      (node (ref "C45") (pin "+") (pinfunction "+_+") (pintype "passive"))
      (node (ref "D20") (pin "C") (pinfunction "C_C") (pintype "passive"))
      (node (ref "R12") (pin "2") (pinfunction "2_2") (pintype "passive"))
      (node (ref "SJ104") (pin "2") (pinfunction "2_2") (pintype "passive"))
      (node (ref "U$1") (pin "P$5") (pinfunction "D4_P$5") (pintype "passive"))
      (node (ref "U$1") (pin "P$6") (pinfunction "D3_P$6") (pintype "passive"))
      (node (ref "U$1") (pin "P$7") (pinfunction "D2_P$7") (pintype "passive"))
      (node (ref "U$1") (pin "P$8") (pinfunction "D1_P$8") (pintype "passive"))
      (node (ref "U$105") (pin "5") (pinfunction "D_5") (pintype "passive"))
      (node (ref "U$105") (pin "6") (pinfunction "D_6") (pintype "passive"))
      (node (ref "U$105") (pin "7") (pinfunction "D_7") (pintype "passive"))
      (node (ref "U$105") (pin "8") (pinfunction "D_8") (pintype "passive"))
      (node (ref "U$108") (pin "5") (pinfunction "D_5") (pintype "passive"))
      (node (ref "U$108") (pin "6") (pinfunction "D_6") (pintype "passive"))
      (node (ref "U$108") (pin "7") (pinfunction "D_7") (pintype "passive"))
      (node (ref "U$108") (pin "8") (pinfunction "D_8") (pintype "passive"))
      (node (ref "U$14") (pin "P$5") (pinfunction "D4_P$5") (pintype "passive"))
      (node (ref "U$14") (pin "P$6") (pinfunction "D3_P$6") (pintype "passive"))
      (node (ref "U$14") (pin "P$7") (pinfunction "D2_P$7") (pintype "passive"))
      (node (ref "U$14") (pin "P$8") (pinfunction "D1_P$8") (pintype "passive"))
      (node (ref "U$15") (pin "P$5") (pinfunction "D4_P$5") (pintype "passive"))
      (node (ref "U$15") (pin "P$6") (pinfunction "D3_P$6") (pintype "passive"))
      (node (ref "U$15") (pin "P$7") (pinfunction "D2_P$7") (pintype "passive"))
      (node (ref "U$15") (pin "P$8") (pinfunction "D1_P$8") (pintype "passive"))
      (node (ref "U$2") (pin "P$5") (pinfunction "D4_P$5") (pintype "passive"))
      (node (ref "U$2") (pin "P$6") (pinfunction "D3_P$6") (pintype "passive"))
      (node (ref "U$2") (pin "P$7") (pinfunction "D2_P$7") (pintype "passive"))
      (node (ref "U$2") (pin "P$8") (pinfunction "D1_P$8") (pintype "passive"))
      (node (ref "U$24") (pin "8") (pinfunction "BATT_8") (pintype "bidirectional"))
      (node (ref "U$25") (pin "8") (pinfunction "BATT_8") (pintype "bidirectional"))
      (node (ref "U$26") (pin "8") (pinfunction "BATT_8") (pintype "bidirectional"))
      (node (ref "U$5") (pin "P$5") (pinfunction "D4_P$5") (pintype "passive"))
      (node (ref "U$5") (pin "P$6") (pinfunction "D3_P$6") (pintype "passive"))
      (node (ref "U$5") (pin "P$7") (pinfunction "D2_P$7") (pintype "passive"))
      (node (ref "U$5") (pin "P$8") (pinfunction "D1_P$8") (pintype "passive"))
      (node (ref "U$6") (pin "P$5") (pinfunction "D4_P$5") (pintype "passive"))
      (node (ref "U$6") (pin "P$6") (pinfunction "D3_P$6") (pintype "passive"))
      (node (ref "U$6") (pin "P$7") (pinfunction "D2_P$7") (pintype "passive"))
      (node (ref "U$6") (pin "P$8") (pinfunction "D1_P$8") (pintype "passive"))
      (node (ref "U$9") (pin "P$5") (pinfunction "D4_P$5") (pintype "passive"))
      (node (ref "U$9") (pin "P$6") (pinfunction "D3_P$6") (pintype "passive"))
      (node (ref "U$9") (pin "P$7") (pinfunction "D2_P$7") (pintype "passive"))
      (node (ref "U$9") (pin "P$8") (pinfunction "D1_P$8") (pintype "passive"))
      (node (ref "X2") (pin "12") (pinfunction "KL_12") (pintype "passive"))
    )
    (net (code "86") (name "VBAT0") (class "Default")
      (node (ref "F3") (pin "1") (pinfunction "1_1") (pintype "bidirectional"))
      (node (ref "U$13") (pin "3") (pinfunction "IP-_3") (pintype "bidirectional"))
      (node (ref "U$13") (pin "4") (pinfunction "IP-_4") (pintype "bidirectional"))
    )
    (net (code "87") (name "VBAT0_X") (class "Default")
      (node (ref "PAD1") (pin "1") (pinfunction "P_1") (pintype "passive"))
      (node (ref "PAD8") (pin "1") (pinfunction "P_1") (pintype "passive"))
      (node (ref "R11") (pin "2") (pinfunction "2_2") (pintype "passive"))
      (node (ref "R27") (pin "2") (pinfunction "2_2") (pintype "passive"))
      (node (ref "R30") (pin "2") (pinfunction "2_2") (pintype "passive"))
      (node (ref "U$12") (pin "P$5") (pinfunction "D4_P$5") (pintype "passive"))
      (node (ref "U$12") (pin "P$6") (pinfunction "D3_P$6") (pintype "passive"))
      (node (ref "U$12") (pin "P$7") (pinfunction "D2_P$7") (pintype "passive"))
      (node (ref "U$12") (pin "P$8") (pinfunction "D1_P$8") (pintype "passive"))
      (node (ref "U$13") (pin "1") (pinfunction "IP+_1") (pintype "bidirectional"))
      (node (ref "U$13") (pin "2") (pinfunction "IP+_2") (pintype "bidirectional"))
      (node (ref "U$20") (pin "8") (pinfunction "BATT_8") (pintype "bidirectional"))
      (node (ref "X2") (pin "1") (pinfunction "KL_1") (pintype "passive"))
      (node (ref "X2") (pin "2") (pinfunction "KL_2") (pintype "passive"))
    )
    (net (code "88") (name "VBAT1") (class "Default")
      (node (ref "F4") (pin "1") (pinfunction "1_1") (pintype "bidirectional"))
      (node (ref "U$11") (pin "3") (pinfunction "IP-_3") (pintype "bidirectional"))
      (node (ref "U$11") (pin "4") (pinfunction "IP-_4") (pintype "bidirectional"))
    )
    (net (code "89") (name "VBAT1_X") (class "Default")
      (node (ref "PAD2") (pin "1") (pinfunction "P_1") (pintype "passive"))
      (node (ref "PAD7") (pin "1") (pinfunction "P_1") (pintype "passive"))
      (node (ref "R15") (pin "2") (pinfunction "2_2") (pintype "passive"))
      (node (ref "R34") (pin "2") (pinfunction "2_2") (pintype "passive"))
      (node (ref "R37") (pin "2") (pinfunction "2_2") (pintype "passive"))
      (node (ref "U$10") (pin "P$5") (pinfunction "D4_P$5") (pintype "passive"))
      (node (ref "U$10") (pin "P$6") (pinfunction "D3_P$6") (pintype "passive"))
      (node (ref "U$10") (pin "P$7") (pinfunction "D2_P$7") (pintype "passive"))
      (node (ref "U$10") (pin "P$8") (pinfunction "D1_P$8") (pintype "passive"))
      (node (ref "U$11") (pin "1") (pinfunction "IP+_1") (pintype "bidirectional"))
      (node (ref "U$11") (pin "2") (pinfunction "IP+_2") (pintype "bidirectional"))
      (node (ref "U$22") (pin "8") (pinfunction "BATT_8") (pintype "bidirectional"))
      (node (ref "X2") (pin "3") (pinfunction "KL_3") (pintype "passive"))
      (node (ref "X2") (pin "4") (pinfunction "KL_4") (pintype "passive"))
    )
    (net (code "90") (name "VBAT2") (class "Default")
      (node (ref "F5") (pin "1") (pinfunction "1_1") (pintype "bidirectional"))
      (node (ref "U$8") (pin "3") (pinfunction "IP-_3") (pintype "bidirectional"))
      (node (ref "U$8") (pin "4") (pinfunction "IP-_4") (pintype "bidirectional"))
    )
    (net (code "91") (name "VBAT2_X") (class "Default")
      (node (ref "PAD3") (pin "1") (pinfunction "P_1") (pintype "passive"))
      (node (ref "PAD6") (pin "1") (pinfunction "P_1") (pintype "passive"))
      (node (ref "R17") (pin "2") (pinfunction "2_2") (pintype "passive"))
      (node (ref "R38") (pin "2") (pinfunction "2_2") (pintype "passive"))
      (node (ref "R43") (pin "2") (pinfunction "2_2") (pintype "passive"))
      (node (ref "U$21") (pin "8") (pinfunction "BATT_8") (pintype "bidirectional"))
      (node (ref "U$7") (pin "P$5") (pinfunction "D4_P$5") (pintype "passive"))
      (node (ref "U$7") (pin "P$6") (pinfunction "D3_P$6") (pintype "passive"))
      (node (ref "U$7") (pin "P$7") (pinfunction "D2_P$7") (pintype "passive"))
      (node (ref "U$7") (pin "P$8") (pinfunction "D1_P$8") (pintype "passive"))
      (node (ref "U$8") (pin "1") (pinfunction "IP+_1") (pintype "bidirectional"))
      (node (ref "U$8") (pin "2") (pinfunction "IP+_2") (pintype "bidirectional"))
      (node (ref "X2") (pin "5") (pinfunction "KL_5") (pintype "passive"))
      (node (ref "X2") (pin "6") (pinfunction "KL_6") (pintype "passive"))
    )
    (net (code "92") (name "VBAT3") (class "Default")
      (node (ref "F6") (pin "1") (pinfunction "1_1") (pintype "bidirectional"))
      (node (ref "U$4") (pin "3") (pinfunction "IP-_3") (pintype "bidirectional"))
      (node (ref "U$4") (pin "4") (pinfunction "IP-_4") (pintype "bidirectional"))
    )
    (net (code "93") (name "VBAT3_X") (class "Default")
      (node (ref "PAD4") (pin "1") (pinfunction "P_1") (pintype "passive"))
      (node (ref "PAD5") (pin "1") (pinfunction "P_1") (pintype "passive"))
      (node (ref "R19") (pin "2") (pinfunction "2_2") (pintype "passive"))
      (node (ref "R44") (pin "2") (pinfunction "2_2") (pintype "passive"))
      (node (ref "R47") (pin "2") (pinfunction "2_2") (pintype "passive"))
      (node (ref "U$23") (pin "8") (pinfunction "BATT_8") (pintype "bidirectional"))
      (node (ref "U$3") (pin "P$5") (pinfunction "D4_P$5") (pintype "passive"))
      (node (ref "U$3") (pin "P$6") (pinfunction "D3_P$6") (pintype "passive"))
      (node (ref "U$3") (pin "P$7") (pinfunction "D2_P$7") (pintype "passive"))
      (node (ref "U$3") (pin "P$8") (pinfunction "D1_P$8") (pintype "passive"))
      (node (ref "U$4") (pin "1") (pinfunction "IP+_1") (pintype "bidirectional"))
      (node (ref "U$4") (pin "2") (pinfunction "IP+_2") (pintype "bidirectional"))
      (node (ref "X2") (pin "7") (pinfunction "KL_7") (pintype "passive"))
      (node (ref "X2") (pin "8") (pinfunction "KL_8") (pintype "passive"))
    )
    (net (code "94") (name "VIN") (class "Default")
      (node (ref "SJ104") (pin "1") (pinfunction "1_1") (pintype "passive"))
      (node (ref "U$17") (pin "P$23") (pinfunction "VIN_P$23") (pintype "bidirectional"))
    )
    (net (code "95") (name "VREF2") (class "Default")
      (node (ref "C10") (pin "1") (pinfunction "1_1") (pintype "passive"))
      (node (ref "C33") (pin "2") (pinfunction "2_2") (pintype "passive"))
      (node (ref "C34") (pin "2") (pinfunction "2_2") (pintype "passive"))
      (node (ref "R23") (pin "2") (pinfunction "2_2") (pintype "passive"))
      (node (ref "R39") (pin "1") (pinfunction "1_1") (pintype "passive"))
      (node (ref "U$17") (pin "P$13") (pinfunction "VREF2_P$13") (pintype "bidirectional"))
      (node (ref "U$17") (pin "P$19") (pinfunction "SKIPSEL2_P$19") (pintype "bidirectional"))
      (node (ref "U$17") (pin "P$6") (pinfunction "SKIPSEL1_P$6") (pintype "bidirectional"))
    )
    (net (code "96") (name "VREG3") (class "Default")
      (node (ref "C17") (pin "2") (pinfunction "2_2") (pintype "passive"))
      (node (ref "R10") (pin "1") (pinfunction "1_1") (pintype "passive"))
      (node (ref "R14") (pin "1") (pinfunction "1_1") (pintype "passive"))
      (node (ref "U$17") (pin "P$22") (pinfunction "VREG3_P$22") (pintype "bidirectional"))
    )
    (net (code "97") (name "X1") (class "Default")
      (node (ref "L1") (pin "2") (pinfunction "2_2") (pintype "passive"))
      (node (ref "SJ108") (pin "2") (pinfunction "2_2") (pintype "passive"))
      (node (ref "U$105") (pin "1") (pinfunction "S_1") (pintype "passive"))
      (node (ref "U$105") (pin "2") (pinfunction "S_2") (pintype "passive"))
      (node (ref "U$105") (pin "3") (pinfunction "S_3") (pintype "passive"))
      (node (ref "U$106") (pin "5") (pinfunction "D_5") (pintype "passive"))
      (node (ref "U$106") (pin "6") (pinfunction "D_6") (pintype "passive"))
      (node (ref "U$106") (pin "7") (pinfunction "D_7") (pintype "passive"))
      (node (ref "U$106") (pin "8") (pinfunction "D_8") (pintype "passive"))
    )
    (net (code "98") (name "X2") (class "Default")
      (node (ref "L2") (pin "1") (pinfunction "1_1") (pintype "passive"))
      (node (ref "SJ110") (pin "2") (pinfunction "2_2") (pintype "passive"))
      (node (ref "U$107") (pin "5") (pinfunction "D_5") (pintype "passive"))
      (node (ref "U$107") (pin "6") (pinfunction "D_6") (pintype "passive"))
      (node (ref "U$107") (pin "7") (pinfunction "D_7") (pintype "passive"))
      (node (ref "U$107") (pin "8") (pinfunction "D_8") (pintype "passive"))
      (node (ref "U$108") (pin "1") (pinfunction "S_1") (pintype "passive"))
      (node (ref "U$108") (pin "2") (pinfunction "S_2") (pintype "passive"))
      (node (ref "U$108") (pin "3") (pinfunction "S_3") (pintype "passive"))
    )
    (net (code "99") (name "unconnected-(U$24-~{LBO}-Pad3)") (class "Default")
      (node (ref "U$24") (pin "3") (pinfunction "~{LBO}_3") (pintype "bidirectional"))
    )
    (net (code "100") (name "unconnected-(U$25-~{LBO}-Pad3)") (class "Default")
      (node (ref "U$25") (pin "3") (pinfunction "~{LBO}_3") (pintype "bidirectional"))
    )
    (net (code "101") (name "unconnected-(U$26-~{LBO}-Pad3)") (class "Default")
      (node (ref "U$26") (pin "3") (pinfunction "~{LBO}_3") (pintype "bidirectional"))
    )
    (net (code "102") (name "~{BAT0_EN}") (class "Default")
      (node (ref "D1") (pin "1") (pinfunction "A1_1") (pintype "passive"))
      (node (ref "Q1") (pin "1") (pinfunction "G_1") (pintype "bidirectional"))
      (node (ref "Q5") (pin "3") (pinfunction "D_3") (pintype "bidirectional"))
      (node (ref "R29") (pin "2") (pinfunction "2_2") (pintype "passive"))
      (node (ref "R30") (pin "1") (pinfunction "1_1") (pintype "passive"))
      (node (ref "U$20") (pin "1") (pinfunction "~{ON}_1") (pintype "bidirectional"))
    )
    (net (code "103") (name "~{BAT1_EN}") (class "Default")
      (node (ref "D1") (pin "2") (pinfunction "A2_2") (pintype "passive"))
      (node (ref "Q2") (pin "1") (pinfunction "G_1") (pintype "bidirectional"))
      (node (ref "Q6") (pin "3") (pinfunction "D_3") (pintype "bidirectional"))
      (node (ref "R36") (pin "2") (pinfunction "2_2") (pintype "passive"))
      (node (ref "R37") (pin "1") (pinfunction "1_1") (pintype "passive"))
      (node (ref "U$22") (pin "1") (pinfunction "~{ON}_1") (pintype "bidirectional"))
    )
    (net (code "104") (name "~{BAT2_EN}") (class "Default")
      (node (ref "D3") (pin "1") (pinfunction "A1_1") (pintype "passive"))
      (node (ref "Q3") (pin "1") (pinfunction "G_1") (pintype "bidirectional"))
      (node (ref "Q7") (pin "3") (pinfunction "D_3") (pintype "bidirectional"))
      (node (ref "R42") (pin "2") (pinfunction "2_2") (pintype "passive"))
      (node (ref "R43") (pin "1") (pinfunction "1_1") (pintype "passive"))
      (node (ref "U$21") (pin "1") (pinfunction "~{ON}_1") (pintype "bidirectional"))
    )
    (net (code "105") (name "~{BAT3_EN}") (class "Default")
      (node (ref "D3") (pin "2") (pinfunction "A2_2") (pintype "passive"))
      (node (ref "Q4") (pin "1") (pinfunction "G_1") (pintype "bidirectional"))
      (node (ref "Q8") (pin "3") (pinfunction "D_3") (pintype "bidirectional"))
      (node (ref "R46") (pin "2") (pinfunction "2_2") (pintype "passive"))
      (node (ref "R47") (pin "1") (pinfunction "1_1") (pintype "passive"))
      (node (ref "U$23") (pin "1") (pinfunction "~{ON}_1") (pintype "bidirectional"))
    )
    (net (code "106") (name "~{OFF_0}") (class "Default")
      (node (ref "Q1") (pin "3") (pinfunction "D_3") (pintype "bidirectional"))
      (node (ref "R27") (pin "1") (pinfunction "1_1") (pintype "passive"))
      (node (ref "R28") (pin "2") (pinfunction "2_2") (pintype "passive"))
      (node (ref "U$20") (pin "2") (pinfunction "~{OFF}_2") (pintype "bidirectional"))
      (node (ref "U$20") (pin "3") (pinfunction "~{LBO}_3") (pintype "bidirectional"))
    )
    (net (code "107") (name "~{OFF_1}") (class "Default")
      (node (ref "Q2") (pin "3") (pinfunction "D_3") (pintype "bidirectional"))
      (node (ref "R34") (pin "1") (pinfunction "1_1") (pintype "passive"))
      (node (ref "R35") (pin "2") (pinfunction "2_2") (pintype "passive"))
      (node (ref "U$22") (pin "2") (pinfunction "~{OFF}_2") (pintype "bidirectional"))
      (node (ref "U$22") (pin "3") (pinfunction "~{LBO}_3") (pintype "bidirectional"))
    )
    (net (code "108") (name "~{OFF_2}") (class "Default")
      (node (ref "Q3") (pin "3") (pinfunction "D_3") (pintype "bidirectional"))
      (node (ref "R38") (pin "1") (pinfunction "1_1") (pintype "passive"))
      (node (ref "R41") (pin "2") (pinfunction "2_2") (pintype "passive"))
      (node (ref "U$21") (pin "2") (pinfunction "~{OFF}_2") (pintype "bidirectional"))
      (node (ref "U$21") (pin "3") (pinfunction "~{LBO}_3") (pintype "bidirectional"))
    )
    (net (code "109") (name "~{OFF_3}") (class "Default")
      (node (ref "Q4") (pin "3") (pinfunction "D_3") (pintype "bidirectional"))
      (node (ref "R44") (pin "1") (pinfunction "1_1") (pintype "passive"))
      (node (ref "R45") (pin "2") (pinfunction "2_2") (pintype "passive"))
      (node (ref "U$23") (pin "2") (pinfunction "~{OFF}_2") (pintype "bidirectional"))
      (node (ref "U$23") (pin "3") (pinfunction "~{LBO}_3") (pintype "bidirectional"))
    )
  )
)
